# can.net
KiCad netlist of a schematic drawn in EAGLE
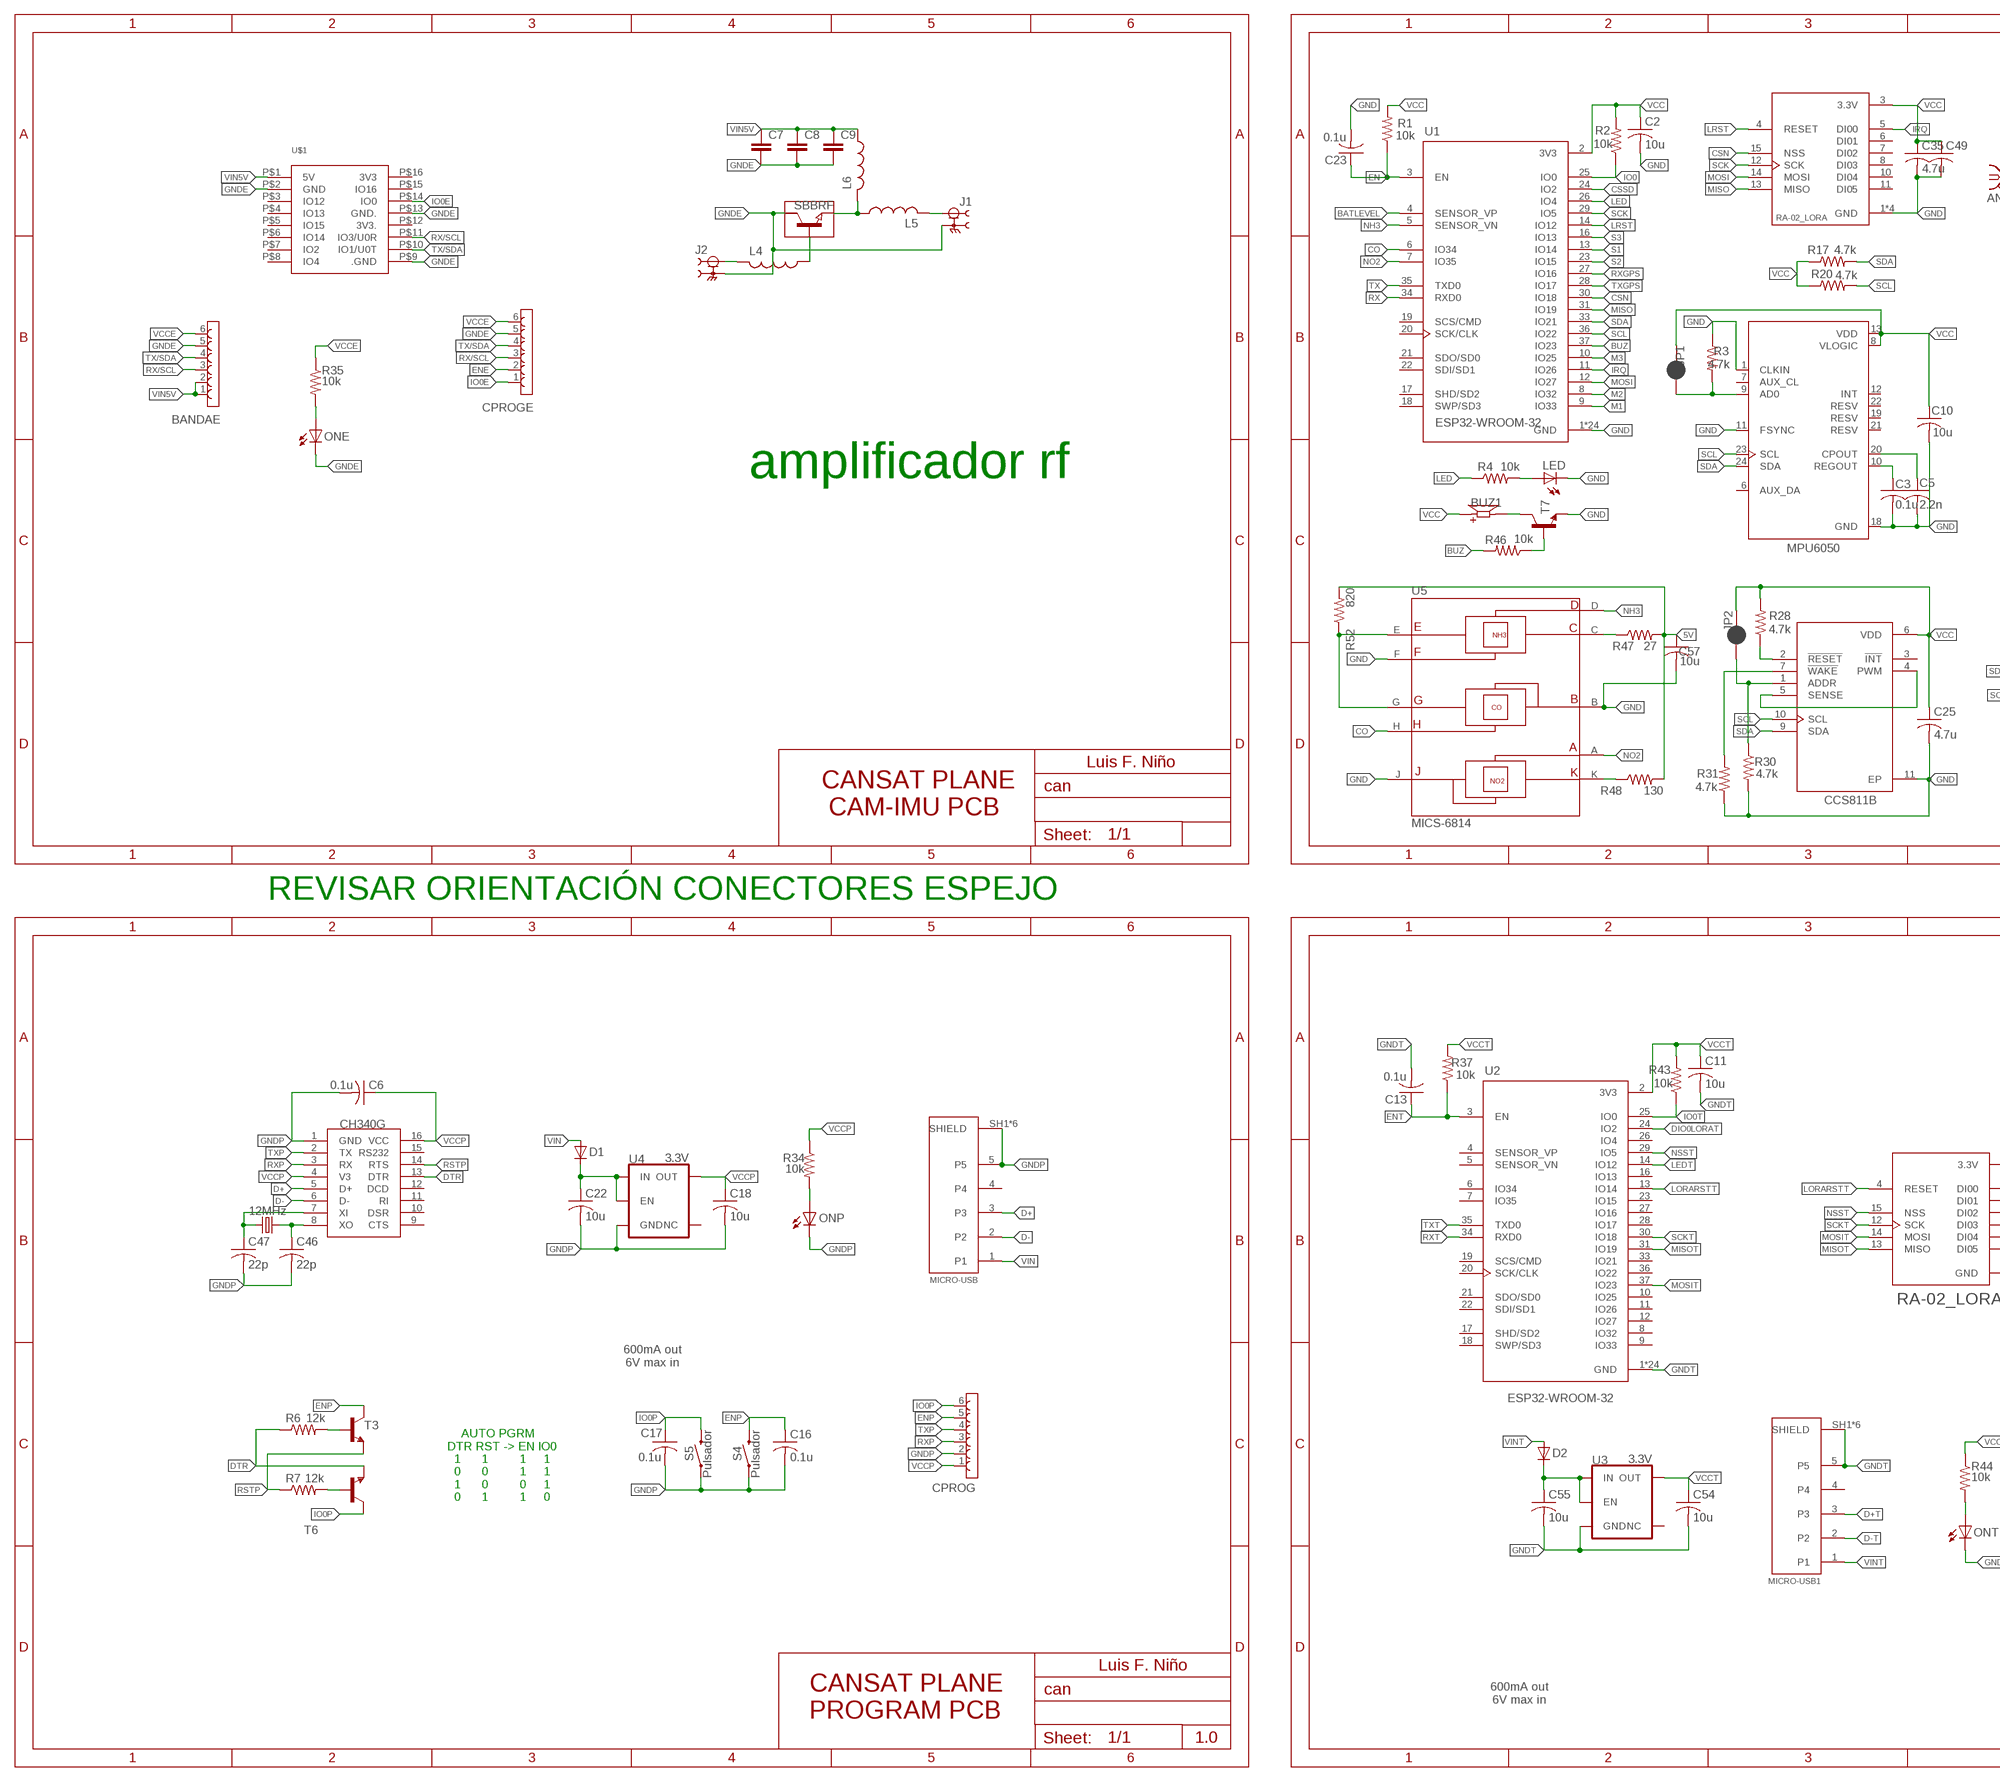
[diagram p0: schematic, sheet 1, part 1 of 2]
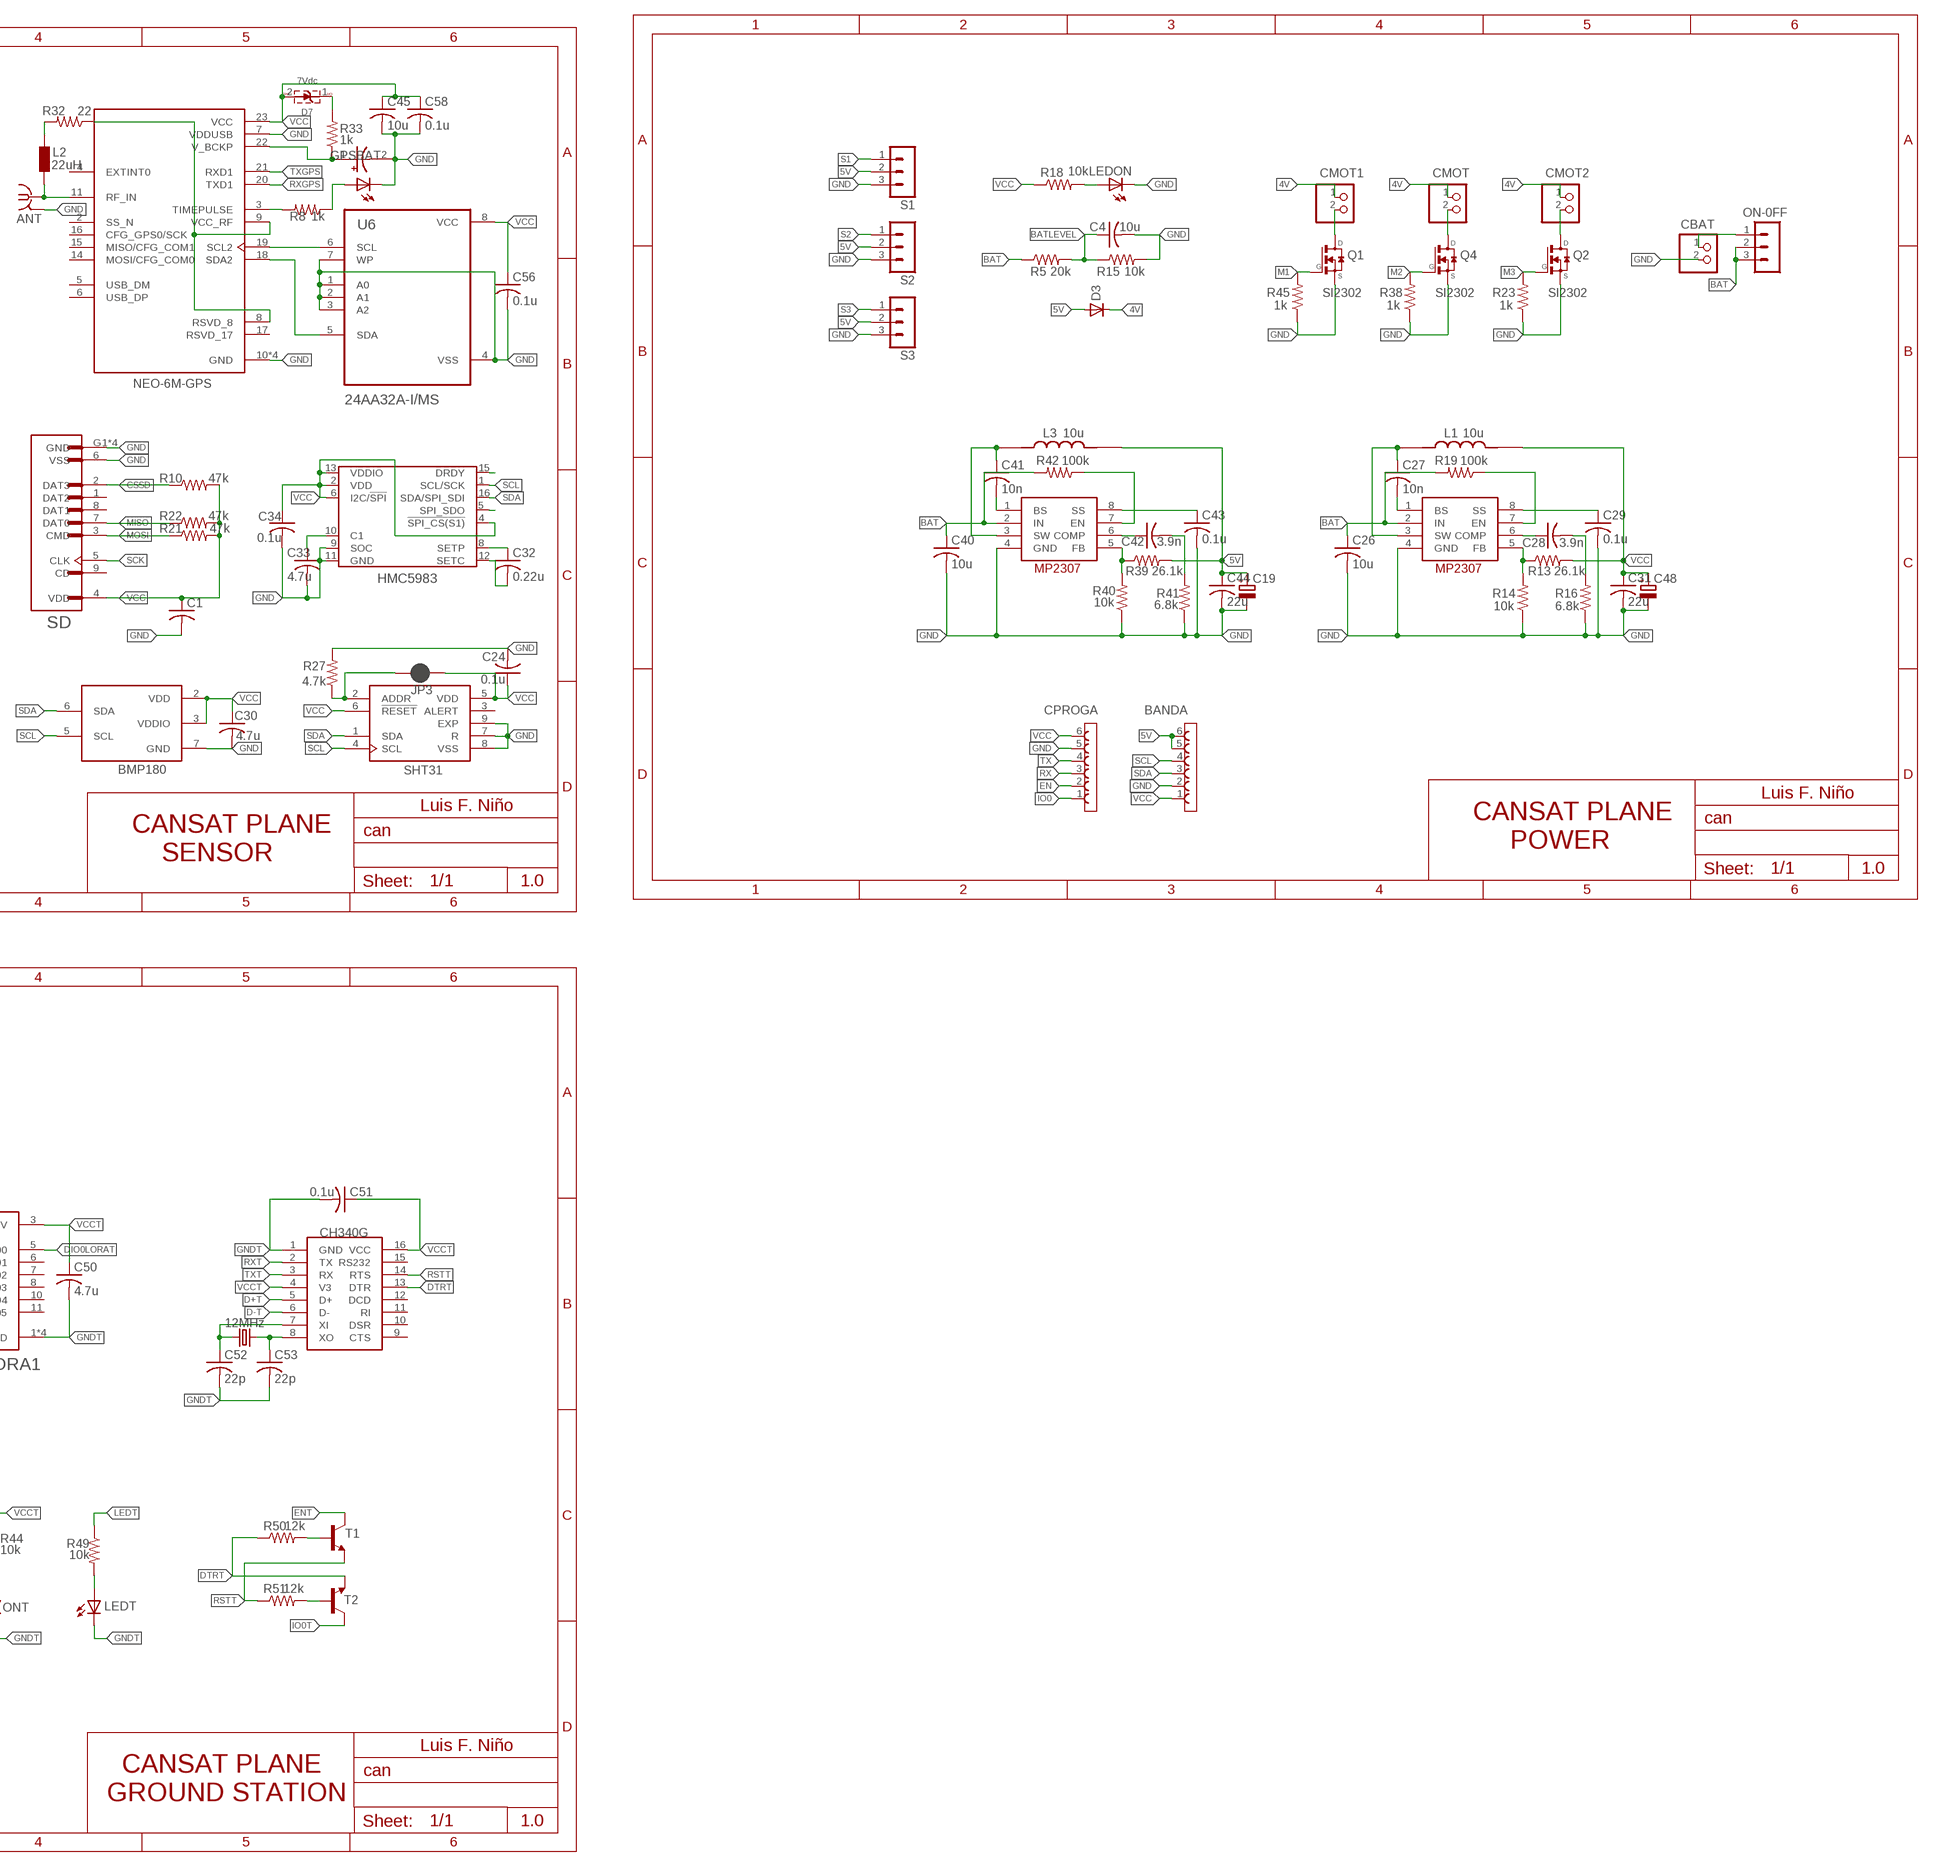
[diagram p1: schematic, sheet 1, part 2 of 2]

(export (version "E")
  (design (tool "Eeschema 10.0.6"))
  (components
    (comp (ref "BANDA")
      (value "68610614122")
      (footprint "eagle-import:68610614122")
      (fields (field (name "MF") "Wurth Electronics"))
      (libsource (lib "eagle-import") (part "68610614122"))
    )
    (comp (ref "BANDAE")
      (value "68610614122")
      (footprint "eagle-import:68610614122")
      (fields (field (name "MF") "Wurth Electronics"))
      (libsource (lib "eagle-import") (part "68610614122"))
    )
    (comp (ref "BMP180")
      (value "BMP180")
      (footprint "eagle-import:BMP180")
      (fields (field (name "MF") "Bosch Sensortec"))
      (libsource (lib "eagle-import") (part "BMP180"))
    )
    (comp (ref "BUZ1")
      (value "BUZ")
      (footprint "eagle-import:CUI_CMT-8530S-SMT")
      (fields (field (name "MF") "CUI Devices") (field (name "MP") "CMT-8530S-SMT-TR"))
      (libsource (lib "eagle-import") (part "CMT-8530S-SMT"))
    )
    (comp (ref "C1")
      (value "C-USC0805K")
      (footprint "eagle-import:C0805K")
      (libsource (lib "eagle-import") (part "C-USC0805K"))
    )
    (comp (ref "C2")
      (value "10u")
      (footprint "eagle-import:C1206")
      (libsource (lib "eagle-import") (part "C-USC1206"))
    )
    (comp (ref "C3")
      (value "0.1u")
      (footprint "eagle-import:C0603K")
      (libsource (lib "eagle-import") (part "C-USC0603K"))
    )
    (comp (ref "C4")
      (value "10u")
      (footprint "eagle-import:C0603K")
      (libsource (lib "eagle-import") (part "C-USC0603K"))
    )
    (comp (ref "C5")
      (value "2.2n")
      (footprint "eagle-import:C0603K")
      (libsource (lib "eagle-import") (part "C-USC0603K"))
    )
    (comp (ref "C6")
      (value "0.1u")
      (footprint "eagle-import:C1206")
      (libsource (lib "eagle-import") (part "C-USC1206"))
    )
    (comp (ref "C7")
      (value "C-EUC0805K")
      (footprint "eagle-import:C0805K")
      (libsource (lib "eagle-import") (part "C-EUC0805K"))
    )
    (comp (ref "C8")
      (value "C-EUC0805K")
      (footprint "eagle-import:C0805K")
      (libsource (lib "eagle-import") (part "C-EUC0805K"))
    )
    (comp (ref "C9")
      (value "C-EUC0805K")
      (footprint "eagle-import:C0805K")
      (libsource (lib "eagle-import") (part "C-EUC0805K"))
    )
    (comp (ref "C10")
      (value "10u")
      (footprint "eagle-import:C1206")
      (libsource (lib "eagle-import") (part "C-USC1206"))
    )
    (comp (ref "C11")
      (value "10u")
      (footprint "eagle-import:C1206")
      (libsource (lib "eagle-import") (part "C-USC1206"))
    )
    (comp (ref "C13")
      (value "0.1u")
      (footprint "eagle-import:C1206")
      (libsource (lib "eagle-import") (part "C-USC1206"))
    )
    (comp (ref "C16")
      (value "0.1u")
      (footprint "eagle-import:C0603K")
      (libsource (lib "eagle-import") (part "resistor_348_C-USC0603K"))
    )
    (comp (ref "C17")
      (value "0.1u")
      (footprint "eagle-import:C0603K")
      (libsource (lib "eagle-import") (part "resistor_348_C-USC0603K"))
    )
    (comp (ref "C18")
      (value "10u")
      (footprint "eagle-import:C1206")
      (libsource (lib "eagle-import") (part "C-USC1206"))
    )
    (comp (ref "C19")
      (value "CPOL-EU153CLV-0605")
      (footprint "eagle-import:153CLV-0605")
      (libsource (lib "eagle-import") (part "CPOL-EU153CLV-0605"))
    )
    (comp (ref "C22")
      (value "10u")
      (footprint "eagle-import:C1206")
      (libsource (lib "eagle-import") (part "C-USC1206"))
    )
    (comp (ref "C23")
      (value "0.1u")
      (footprint "eagle-import:C1206")
      (libsource (lib "eagle-import") (part "C-USC1206"))
    )
    (comp (ref "C24")
      (value "0.1u")
      (footprint "eagle-import:C1206")
      (libsource (lib "eagle-import") (part "C-USC1206"))
    )
    (comp (ref "C25")
      (value "4.7u")
      (footprint "eagle-import:C1206")
      (libsource (lib "eagle-import") (part "C-USC1206"))
    )
    (comp (ref "C26")
      (value "10u")
      (footprint "eagle-import:C1206")
      (libsource (lib "eagle-import") (part "C-USC1206"))
    )
    (comp (ref "C27")
      (value "10n")
      (footprint "eagle-import:C0805")
      (libsource (lib "eagle-import") (part "C-USC0805"))
    )
    (comp (ref "C28")
      (value "3.9n")
      (footprint "eagle-import:C0805")
      (libsource (lib "eagle-import") (part "C-USC0805"))
    )
    (comp (ref "C29")
      (value "0.1u")
      (footprint "eagle-import:C0805")
      (libsource (lib "eagle-import") (part "C-USC0805"))
    )
    (comp (ref "C30")
      (value "4.7u")
      (footprint "eagle-import:C1206")
      (libsource (lib "eagle-import") (part "C-USC1206"))
    )
    (comp (ref "C31")
      (value "22u")
      (footprint "eagle-import:C1206")
      (libsource (lib "eagle-import") (part "C-USC1206"))
    )
    (comp (ref "C32")
      (value "0.22u")
      (footprint "eagle-import:C0603K")
      (libsource (lib "eagle-import") (part "C-USC0603K"))
    )
    (comp (ref "C33")
      (value "4.7u")
      (footprint "eagle-import:C0603K")
      (libsource (lib "eagle-import") (part "C-USC0603K"))
    )
    (comp (ref "C34")
      (value "0.1u")
      (footprint "eagle-import:C1206")
      (libsource (lib "eagle-import") (part "C-USC1206"))
    )
    (comp (ref "C35")
      (value "4.7u")
      (footprint "eagle-import:C1206")
      (libsource (lib "eagle-import") (part "C-USC1206"))
    )
    (comp (ref "C40")
      (value "10u")
      (footprint "eagle-import:C1206")
      (libsource (lib "eagle-import") (part "C-USC1206"))
    )
    (comp (ref "C41")
      (value "10n")
      (footprint "eagle-import:C0805")
      (libsource (lib "eagle-import") (part "C-USC0805"))
    )
    (comp (ref "C42")
      (value "3.9n")
      (footprint "eagle-import:C0805")
      (libsource (lib "eagle-import") (part "C-USC0805"))
    )
    (comp (ref "C43")
      (value "0.1u")
      (footprint "eagle-import:C0805")
      (libsource (lib "eagle-import") (part "C-USC0805"))
    )
    (comp (ref "C44")
      (value "22u")
      (footprint "eagle-import:C1206")
      (libsource (lib "eagle-import") (part "C-USC1206"))
    )
    (comp (ref "C45")
      (value "10u")
      (footprint "eagle-import:C1206")
      (libsource (lib "eagle-import") (part "C-USC1206"))
    )
    (comp (ref "C46")
      (value "22p")
      (footprint "eagle-import:C1206")
      (libsource (lib "eagle-import") (part "C-USC1206"))
    )
    (comp (ref "C47")
      (value "22p")
      (footprint "eagle-import:C1206")
      (libsource (lib "eagle-import") (part "C-USC1206"))
    )
    (comp (ref "C48")
      (value "CPOL-EU153CLV-0605")
      (footprint "eagle-import:153CLV-0605")
      (libsource (lib "eagle-import") (part "CPOL-EU153CLV-0605"))
    )
    (comp (ref "C49")
      (value "C-USC0805K")
      (footprint "eagle-import:C0805K")
      (libsource (lib "eagle-import") (part "C-USC0805K"))
    )
    (comp (ref "C50")
      (value "4.7u")
      (footprint "eagle-import:C1206")
      (libsource (lib "eagle-import") (part "C-USC1206"))
    )
    (comp (ref "C51")
      (value "0.1u")
      (footprint "eagle-import:C1206")
      (libsource (lib "eagle-import") (part "C-USC1206"))
    )
    (comp (ref "C52")
      (value "22p")
      (footprint "eagle-import:C1206")
      (libsource (lib "eagle-import") (part "C-USC1206"))
    )
    (comp (ref "C53")
      (value "22p")
      (footprint "eagle-import:C1206")
      (libsource (lib "eagle-import") (part "C-USC1206"))
    )
    (comp (ref "C54")
      (value "10u")
      (footprint "eagle-import:C1206")
      (libsource (lib "eagle-import") (part "C-USC1206"))
    )
    (comp (ref "C55")
      (value "10u")
      (footprint "eagle-import:C1206")
      (libsource (lib "eagle-import") (part "C-USC1206"))
    )
    (comp (ref "C56")
      (value "0.1u")
      (footprint "eagle-import:C0805K")
      (libsource (lib "eagle-import") (part "C-USC0805K"))
    )
    (comp (ref "C57")
      (value "10u")
      (footprint "eagle-import:C1206")
      (libsource (lib "eagle-import") (part "C-USC1206"))
    )
    (comp (ref "C58")
      (value "0.1u")
      (footprint "eagle-import:C0805K")
      (libsource (lib "eagle-import") (part "C-USC0805K"))
    )
    (comp (ref "CBAT")
      (value "PINHD-1X2")
      (footprint "eagle-import:1X02")
      (libsource (lib "eagle-import") (part "PINHD-1X2"))
    )
    (comp (ref "CCS811B")
      (value "CCS811B-JOPD500")
      (footprint "eagle-import:SON60P400X270X110-11N")
      (fields (field (name "MF") "ScioSense"))
      (libsource (lib "eagle-import") (part "CCS811B-JOPD500"))
    )
    (comp (ref "CH1")
      (value "CH340")
      (footprint "eagle-import:SOIC127P600X175-16N")
      (fields (field (name "MF") "WCH") (field (name "MP") "Ch340G"))
      (libsource (lib "eagle-import") (part "CH340G"))
    )
    (comp (ref "CH340")
      (value "CH340")
      (footprint "eagle-import:SOIC127P600X175-16N")
      (fields (field (name "MF") "WCH") (field (name "MP") "Ch340G"))
      (libsource (lib "eagle-import") (part "CH340G"))
    )
    (comp (ref "CMOT")
      (value "PINHD-1X2")
      (footprint "eagle-import:1X02")
      (libsource (lib "eagle-import") (part "PINHD-1X2"))
    )
    (comp (ref "CMOT1")
      (value "PINHD-1X2")
      (footprint "eagle-import:1X02")
      (libsource (lib "eagle-import") (part "PINHD-1X2"))
    )
    (comp (ref "CMOT2")
      (value "PINHD-1X2")
      (footprint "eagle-import:1X02")
      (libsource (lib "eagle-import") (part "PINHD-1X2"))
    )
    (comp (ref "CPROG")
      (value "68610614122")
      (footprint "eagle-import:68610614122")
      (fields (field (name "MF") "Wurth Electronics"))
      (libsource (lib "eagle-import") (part "68610614122"))
    )
    (comp (ref "CPROGA")
      (value "68610614122")
      (footprint "eagle-import:68610614122")
      (fields (field (name "MF") "Wurth Electronics"))
      (libsource (lib "eagle-import") (part "68610614122"))
    )
    (comp (ref "CPROGE")
      (value "68610614122")
      (footprint "eagle-import:68610614122")
      (fields (field (name "MF") "Wurth Electronics"))
      (libsource (lib "eagle-import") (part "68610614122"))
    )
    (comp (ref "D1")
      (value "CGRM4005-G")
      (footprint "eagle-import:SOD-123_MINI-SMA")
      (libsource (lib "eagle-import") (part "CGRM400-G5"))
    )
    (comp (ref "D2")
      (value "CGRM4005-G")
      (footprint "eagle-import:SOD-123_MINI-SMA")
      (libsource (lib "eagle-import") (part "CGRM400-G5"))
    )
    (comp (ref "D3")
      (value "CGRM4005-G")
      (footprint "eagle-import:SOD-123_MINI-SMA")
      (libsource (lib "eagle-import") (part "CGRM400-G5"))
    )
    (comp (ref "D7")
      (value "7Vdc")
      (footprint "eagle-import:WE-TVS_DFN1610-2L")
      (libsource (lib "eagle-import") (part "WE-TVS_DFN1610-2L_824045817"))
    )
    (comp (ref "GPSBAT")
      (value "XH414H")
      (footprint "eagle-import:CAP_XH414H-IV01E")
      (fields (field (name "MF") "Seiko Instruments") (field (name "MP") "XH414H-IV01E"))
      (libsource (lib "eagle-import") (part "XH414H-IV01E"))
    )
    (comp (ref "HMC5983")
      (value "HMC5983")
      (footprint "eagle-import:HMC5983")
      (fields (field (name "MF") "Honeywell Aerospace") (field (name "MP") "HMC5983-T"))
      (libsource (lib "eagle-import") (part "HMC5983"))
    )
    (comp (ref "IC2")
      (value "MP2307")
      (footprint "eagle-import:SO8-TH")
      (fields (field (name "MF") "Monolithic Power"))
      (libsource (lib "eagle-import") (part "MP2307"))
    )
    (comp (ref "IC4")
      (value "MP2307")
      (footprint "eagle-import:SO8-TH")
      (fields (field (name "MF") "Monolithic Power"))
      (libsource (lib "eagle-import") (part "MP2307"))
    )
    (comp (ref "J1")
      (value "CONSMA003.031-G")
      (footprint "eagle-import:LINX_CONSMA003.031-G")
      (fields (field (name "MF") "Linx Technologies"))
      (libsource (lib "eagle-import") (part "CONSMA003.031-G"))
    )
    (comp (ref "J2")
      (value "CONSMA003.031-G")
      (footprint "eagle-import:LINX_CONSMA003.031-G")
      (fields (field (name "MF") "Linx Technologies"))
      (libsource (lib "eagle-import") (part "CONSMA003.031-G"))
    )
    (comp (ref "JP1")
      (value "JUMPER-SMT_2_NC_PASTE_SILK")
      (footprint "eagle-import:SMT-JUMPER_2_NC_PASTE_SILK")
      (libsource (lib "eagle-import") (part "JUMPER-SMT_2_NC_PASTE_SILK"))
    )
    (comp (ref "JP2")
      (value "JUMPER-SMT_2_NC_PASTE_SILK")
      (footprint "eagle-import:SMT-JUMPER_2_NC_PASTE_SILK")
      (libsource (lib "eagle-import") (part "JUMPER-SMT_2_NC_PASTE_SILK"))
    )
    (comp (ref "JP3")
      (value "JUMPER-SMT_2_NC_PASTE_SILK")
      (footprint "eagle-import:SMT-JUMPER_2_NC_PASTE_SILK")
      (libsource (lib "eagle-import") (part "JUMPER-SMT_2_NC_PASTE_SILK"))
    )
    (comp (ref "L1")
      (value "10u")
      (footprint "eagle-import:IND_FDVE0630-H-100M=P3")
      (fields (field (name "MF") "Murata") (field (name "MP") "FDVE0630-H-100M=P3"))
      (libsource (lib "eagle-import") (part "FDVE0630-H-100M=P3"))
    )
    (comp (ref "L2")
      (value "22uH")
      (footprint "eagle-import:L2012C")
      (libsource (lib "eagle-import") (part "LL2012C"))
    )
    (comp (ref "L3")
      (value "10u")
      (footprint "eagle-import:IND_FDVE0630-H-100M=P3")
      (fields (field (name "MF") "Murata") (field (name "MP") "FDVE0630-H-100M=P3"))
      (libsource (lib "eagle-import") (part "FDVE0630-H-100M=P3"))
    )
    (comp (ref "L4")
      (value "L-USL2012C")
      (footprint "eagle-import:L2012C")
      (libsource (lib "eagle-import") (part "L-USL2012C"))
    )
    (comp (ref "L5")
      (value "L-USL2012C")
      (footprint "eagle-import:L2012C")
      (libsource (lib "eagle-import") (part "L-USL2012C"))
    )
    (comp (ref "L6")
      (value "L-USL3225P")
      (footprint "eagle-import:L3225P")
      (libsource (lib "eagle-import") (part "L-USL3225P"))
    )
    (comp (ref "LED")
      (value "LEDCHIPLED_0805")
      (footprint "eagle-import:CHIPLED_0805")
      (libsource (lib "eagle-import") (part "LEDCHIPLED_0805"))
    )
    (comp (ref "LED1")
      (value "LEDCHIPLED_0805")
      (footprint "eagle-import:CHIPLED_0805")
      (libsource (lib "eagle-import") (part "LEDCHIPLED_0805"))
    )
    (comp (ref "LEDON")
      (value "LEDCHIPLED_0805")
      (footprint "eagle-import:CHIPLED_0805")
      (libsource (lib "eagle-import") (part "LEDCHIPLED_0805"))
    )
    (comp (ref "LEDT")
      (value "LEDCHIPLED_0805")
      (footprint "eagle-import:CHIPLED_0805")
      (libsource (lib "eagle-import") (part "LEDCHIPLED_0805"))
    )
    (comp (ref "MICRO-USB")
      (value "1932788-1")
      (footprint "eagle-import:TE_1932788-1")
      (fields (field (name "MF") "TE Connectivity"))
      (libsource (lib "eagle-import") (part "1932788-1"))
    )
    (comp (ref "MICRO-USB1")
      (value "1932788-1")
      (footprint "eagle-import:TE_1932788-1")
      (fields (field (name "MF") "TE Connectivity"))
      (libsource (lib "eagle-import") (part "1932788-1"))
    )
    (comp (ref "MPU6050")
      (value "MPU-6050")
      (footprint "eagle-import:QFN50P400X400X95-24N")
      (fields (field (name "MF") "TDK InvenSense"))
      (libsource (lib "eagle-import") (part "MPU-6050"))
    )
    (comp (ref "NEO-6M-GPS")
      (value "NEO-6M-GPS")
      (footprint "eagle-import:XCVR_NEO-6M-GPS")
      (fields (field (name "MF") "u-blox"))
      (libsource (lib "eagle-import") (part "NEO-6M-GPS"))
    )
    (comp (ref "ON-0FF")
      (value "MA03-1")
      (footprint "eagle-import:MA03-1")
      (libsource (lib "eagle-import") (part "MA03-1"))
    )
    (comp (ref "ONE")
      (value "LEDCHIPLED_0805")
      (footprint "eagle-import:CHIPLED_0805")
      (libsource (lib "eagle-import") (part "LEDCHIPLED_0805"))
    )
    (comp (ref "ONP")
      (value "LEDCHIPLED_0805")
      (footprint "eagle-import:CHIPLED_0805")
      (libsource (lib "eagle-import") (part "LEDCHIPLED_0805"))
    )
    (comp (ref "ONT")
      (value "LEDCHIPLED_0805")
      (footprint "eagle-import:CHIPLED_0805")
      (libsource (lib "eagle-import") (part "LEDCHIPLED_0805"))
    )
    (comp (ref "Q1")
      (value "SI2302")
      (footprint "eagle-import:SOT23")
      (fields (field (name "MF") "Vishay Siliconix"))
      (libsource (lib "eagle-import") (part "SI2302"))
    )
    (comp (ref "Q2")
      (value "SI2302")
      (footprint "eagle-import:SOT23")
      (fields (field (name "MF") "Vishay Siliconix"))
      (libsource (lib "eagle-import") (part "SI2302"))
    )
    (comp (ref "Q4")
      (value "SI2302")
      (footprint "eagle-import:SOT23")
      (fields (field (name "MF") "Vishay Siliconix"))
      (libsource (lib "eagle-import") (part "SI2302"))
    )
    (comp (ref "R1")
      (value "10k")
      (footprint "eagle-import:R0603")
      (libsource (lib "eagle-import") (part "resistor_348_R-US_R0603"))
    )
    (comp (ref "R2")
      (value "10k")
      (footprint "eagle-import:R0603")
      (libsource (lib "eagle-import") (part "resistor_348_R-US_R0603"))
    )
    (comp (ref "R3")
      (value "4.7k")
      (footprint "eagle-import:R0603")
      (libsource (lib "eagle-import") (part "R-US_R0603"))
    )
    (comp (ref "R4")
      (value "10k")
      (footprint "eagle-import:R0603")
      (libsource (lib "eagle-import") (part "resistor_348_R-US_R0603"))
    )
    (comp (ref "R5")
      (value "20k")
      (footprint "eagle-import:R0603")
      (libsource (lib "eagle-import") (part "resistor_348_R-US_R0603"))
    )
    (comp (ref "R6")
      (value "12k")
      (footprint "eagle-import:R0603")
      (libsource (lib "eagle-import") (part "resistor_348_R-US_R0603"))
    )
    (comp (ref "R7")
      (value "12k")
      (footprint "eagle-import:R0603")
      (libsource (lib "eagle-import") (part "resistor_348_R-US_R0603"))
    )
    (comp (ref "R8")
      (value "1k")
      (footprint "eagle-import:R0603")
      (libsource (lib "eagle-import") (part "resistor_348_R-US_R0603"))
    )
    (comp (ref "R10")
      (value "47k")
      (footprint "eagle-import:R0603")
      (libsource (lib "eagle-import") (part "resistor_348_R-US_R0603"))
    )
    (comp (ref "R13")
      (value "26.1k")
      (footprint "eagle-import:M0805")
      (libsource (lib "eagle-import") (part "R-US_M0805"))
    )
    (comp (ref "R14")
      (value "10k")
      (footprint "eagle-import:R0603")
      (libsource (lib "eagle-import") (part "resistor_348_R-US_R0603"))
    )
    (comp (ref "R15")
      (value "10k")
      (footprint "eagle-import:R0603")
      (libsource (lib "eagle-import") (part "resistor_348_R-US_R0603"))
    )
    (comp (ref "R16")
      (value "6.8k")
      (footprint "eagle-import:R0603")
      (libsource (lib "eagle-import") (part "resistor_348_R-US_R0603"))
    )
    (comp (ref "R17")
      (value "4.7k")
      (footprint "eagle-import:R0603")
      (libsource (lib "eagle-import") (part "resistor_348_R-US_R0603"))
    )
    (comp (ref "R18")
      (value "10k")
      (footprint "eagle-import:R0603")
      (libsource (lib "eagle-import") (part "resistor_348_R-US_R0603"))
    )
    (comp (ref "R19")
      (value "100k")
      (footprint "eagle-import:R0603")
      (libsource (lib "eagle-import") (part "resistor_348_R-US_R0603"))
    )
    (comp (ref "R20")
      (value "4.7k")
      (footprint "eagle-import:R0603")
      (libsource (lib "eagle-import") (part "resistor_348_R-US_R0603"))
    )
    (comp (ref "R21")
      (value "47k")
      (footprint "eagle-import:R0603")
      (libsource (lib "eagle-import") (part "resistor_348_R-US_R0603"))
    )
    (comp (ref "R22")
      (value "47k")
      (footprint "eagle-import:R0603")
      (libsource (lib "eagle-import") (part "resistor_348_R-US_R0603"))
    )
    (comp (ref "R23")
      (value "1k")
      (footprint "eagle-import:R0603")
      (libsource (lib "eagle-import") (part "resistor_348_R-US_R0603"))
    )
    (comp (ref "R27")
      (value "4.7k")
      (footprint "eagle-import:R0603")
      (libsource (lib "eagle-import") (part "resistor_348_R-US_R0603"))
    )
    (comp (ref "R28")
      (value "4.7k")
      (footprint "eagle-import:R0603")
      (libsource (lib "eagle-import") (part "resistor_348_R-US_R0603"))
    )
    (comp (ref "R30")
      (value "4.7k")
      (footprint "eagle-import:R0603")
      (libsource (lib "eagle-import") (part "resistor_348_R-US_R0603"))
    )
    (comp (ref "R31")
      (value "4.7k")
      (footprint "eagle-import:R0603")
      (libsource (lib "eagle-import") (part "resistor_348_R-US_R0603"))
    )
    (comp (ref "R32")
      (value "22")
      (footprint "eagle-import:R0603")
      (libsource (lib "eagle-import") (part "resistor_348_R-US_R0603"))
    )
    (comp (ref "R33")
      (value "1k")
      (footprint "eagle-import:R0603")
      (libsource (lib "eagle-import") (part "resistor_348_R-US_R0603"))
    )
    (comp (ref "R34")
      (value "10k")
      (footprint "eagle-import:R0603")
      (libsource (lib "eagle-import") (part "resistor_348_R-US_R0603"))
    )
    (comp (ref "R35")
      (value "10k")
      (footprint "eagle-import:R0603")
      (libsource (lib "eagle-import") (part "resistor_348_R-US_R0603"))
    )
    (comp (ref "R37")
      (value "10k")
      (footprint "eagle-import:R0603")
      (libsource (lib "eagle-import") (part "resistor_348_R-US_R0603"))
    )
    (comp (ref "R38")
      (value "1k")
      (footprint "eagle-import:R0603")
      (libsource (lib "eagle-import") (part "resistor_348_R-US_R0603"))
    )
    (comp (ref "R39")
      (value "26.1k")
      (footprint "eagle-import:M0805")
      (libsource (lib "eagle-import") (part "R-US_M0805"))
    )
    (comp (ref "R40")
      (value "10k")
      (footprint "eagle-import:R0603")
      (libsource (lib "eagle-import") (part "resistor_348_R-US_R0603"))
    )
    (comp (ref "R41")
      (value "6.8k")
      (footprint "eagle-import:R0603")
      (libsource (lib "eagle-import") (part "resistor_348_R-US_R0603"))
    )
    (comp (ref "R42")
      (value "100k")
      (footprint "eagle-import:R0603")
      (libsource (lib "eagle-import") (part "resistor_348_R-US_R0603"))
    )
    (comp (ref "R43")
      (value "10k")
      (footprint "eagle-import:R0603")
      (libsource (lib "eagle-import") (part "resistor_348_R-US_R0603"))
    )
    (comp (ref "R44")
      (value "10k")
      (footprint "eagle-import:R0603")
      (libsource (lib "eagle-import") (part "resistor_348_R-US_R0603"))
    )
    (comp (ref "R45")
      (value "1k")
      (footprint "eagle-import:R0603")
      (libsource (lib "eagle-import") (part "resistor_348_R-US_R0603"))
    )
    (comp (ref "R46")
      (value "10k")
      (footprint "eagle-import:R0603")
      (libsource (lib "eagle-import") (part "resistor_348_R-US_R0603"))
    )
    (comp (ref "R47")
      (value "27")
      (footprint "eagle-import:R0603")
      (libsource (lib "eagle-import") (part "resistor_348_R-US_R0603"))
    )
    (comp (ref "R48")
      (value "130")
      (footprint "eagle-import:R0603")
      (libsource (lib "eagle-import") (part "resistor_348_R-US_R0603"))
    )
    (comp (ref "R49")
      (value "10k")
      (footprint "eagle-import:R0603")
      (libsource (lib "eagle-import") (part "resistor_348_R-US_R0603"))
    )
    (comp (ref "R50")
      (value "12k")
      (footprint "eagle-import:R0603")
      (libsource (lib "eagle-import") (part "resistor_348_R-US_R0603"))
    )
    (comp (ref "R51")
      (value "12k")
      (footprint "eagle-import:R0603")
      (libsource (lib "eagle-import") (part "resistor_348_R-US_R0603"))
    )
    (comp (ref "R52")
      (value "820")
      (footprint "eagle-import:R0603")
      (libsource (lib "eagle-import") (part "resistor_348_R-US_R0603"))
    )
    (comp (ref "RA-02_LORA")
      (value "RA-02_LORA")
      (footprint "eagle-import:MODULE_RA-02_LORA")
      (fields (field (name "MF") "AI-Thinker") (field (name "MP") "Ra-02 LoRa"))
      (libsource (lib "eagle-import") (part "RA-02_LORA"))
    )
    (comp (ref "RA-02_LORA1")
      (value "RA-02_LORA")
      (footprint "eagle-import:MODULE_RA-02_LORA")
      (fields (field (name "MF") "AI-Thinker") (field (name "MP") "Ra-02 LoRa"))
      (libsource (lib "eagle-import") (part "RA-02_LORA"))
    )
    (comp (ref "S1")
      (value "MA03-1")
      (footprint "eagle-import:MA03-1")
      (libsource (lib "eagle-import") (part "MA03-1"))
    )
    (comp (ref "S2")
      (value "MA03-1")
      (footprint "eagle-import:MA03-1")
      (libsource (lib "eagle-import") (part "MA03-1"))
    )
    (comp (ref "S3")
      (value "MA03-1")
      (footprint "eagle-import:MA03-1")
      (libsource (lib "eagle-import") (part "MA03-1"))
    )
    (comp (ref "S4")
      (value "Pulsador")
      (footprint "eagle-import:TACTILE_SWITCH_SMD_RIGHT_ANGLE")
      (libsource (lib "eagle-import") (part "MOMENTARY-SWITCH-SPST-SMD-RIGHT-ANGLE"))
    )
    (comp (ref "S5")
      (value "Pulsador")
      (footprint "eagle-import:TACTILE_SWITCH_SMD_RIGHT_ANGLE")
      (libsource (lib "eagle-import") (part "MOMENTARY-SWITCH-SPST-SMD-RIGHT-ANGLE"))
    )
    (comp (ref "SBBRF")
      (value "NPN-TRANSISTIOR-2COLSOT89")
      (footprint "eagle-import:SOT89")
      (libsource (lib "eagle-import") (part "NPN-TRANSISTIOR-2COLSOT89"))
    )
    (comp (ref "SD")
      (value "ST-TF-003A")
      (footprint "eagle-import:SUNTECH_ST-TF-003A")
      (fields (field (name "MF") "Suntech"))
      (libsource (lib "eagle-import") (part "ST-TF-003A"))
    )
    (comp (ref "SHT31")
      (value "SHT31-DIS-B")
      (footprint "eagle-import:SON50P250X250X100-9N")
      (fields (field (name "MF") "Sensirion AG"))
      (libsource (lib "eagle-import") (part "SHT31-DIS-B"))
    )
    (comp (ref "T1")
      (value "MMBT2222ALT1-NPN-SOT23-BEC")
      (footprint "eagle-import:SOT23-BEC")
      (libsource (lib "eagle-import") (part "transistor_402_-NPN-SOT23-BECMMBT2222ALT1"))
    )
    (comp (ref "T2")
      (value "MMBT2222ALT1-NPN-SOT23-BEC")
      (footprint "eagle-import:SOT23-BEC")
      (libsource (lib "eagle-import") (part "transistor_402_-NPN-SOT23-BECMMBT2222ALT1"))
    )
    (comp (ref "T3")
      (value "MMBT2222ALT1-NPN-SOT23-BEC")
      (footprint "eagle-import:SOT23-BEC")
      (libsource (lib "eagle-import") (part "transistor_402_-NPN-SOT23-BECMMBT2222ALT1"))
    )
    (comp (ref "T6")
      (value "MMBT2222ALT1-NPN-SOT23-BEC")
      (footprint "eagle-import:SOT23-BEC")
      (libsource (lib "eagle-import") (part "transistor_402_-NPN-SOT23-BECMMBT2222ALT1"))
    )
    (comp (ref "T7")
      (value "MMBT2222ALT1-NPN-SOT23-BEC")
      (footprint "eagle-import:SOT23-BEC")
      (libsource (lib "eagle-import") (part "-NPN-SOT23-BECMMBT2222ALT1"))
    )
    (comp (ref "U$1")
      (value "ESP32-CAM")
      (footprint "eagle-import:ESP32-CAM")
      (fields (field (name "MF") "AI-Thinker"))
      (libsource (lib "eagle-import") (part "ESP32-CAM"))
    )
    (comp (ref "U1")
      (value "ESP32-WROOM-32")
      (footprint "eagle-import:MODULE_ESP32-WROOM-32")
      (fields (field (name "MF") "Espressif Systems") (field (name "SPICEPREFIX") "X"))
      (libsource (lib "eagle-import") (part "ESP32-WROOM-32"))
    )
    (comp (ref "U2")
      (value "ESP32-WROOM-32")
      (footprint "eagle-import:MODULE_ESP32-WROOM-32")
      (fields (field (name "MF") "Espressif Systems"))
      (libsource (lib "eagle-import") (part "ESP32-WROOM-32"))
    )
    (comp (ref "U3")
      (value "3.3V")
      (footprint "eagle-import:SOT23-5")
      (libsource (lib "eagle-import") (part "V_REG_AP2112K-3.3V"))
    )
    (comp (ref "U4")
      (value "3.3V")
      (footprint "eagle-import:SOT23-5")
      (libsource (lib "eagle-import") (part "V_REG_AP2112K-3.3V"))
    )
    (comp (ref "U5")
      (value "MICS-6814")
      (footprint "eagle-import:SENSOR_MICS-6814")
      (fields (field (name "MF") "Amphenol SGX Sensortech"))
      (libsource (lib "eagle-import") (part "MICS-6814"))
    )
    (comp (ref "U6")
      (value "24AA32A-I/MS")
      (footprint "eagle-import:SOP65P490X110-8N")
      (fields (field (name "MF") "Microchip"))
      (libsource (lib "eagle-import") (part "24AA32A-I/MS"))
    )
    (comp (ref "X2")
      (value "ANT")
      (footprint "eagle-import:MC-921")
      (libsource (lib "eagle-import") (part "MC-921"))
    )
    (comp (ref "Y2")
      (value "12MHz")
      (footprint "eagle-import:CRYSTAL-SMD-3.2X2.5MM")
      (libsource (lib "eagle-import") (part "CRYSTALSMD-3.2X2.5"))
    )
    (comp (ref "Y3")
      (value "12MHz")
      (footprint "eagle-import:CRYSTAL-SMD-3.2X2.5MM")
      (libsource (lib "eagle-import") (part "CRYSTALSMD-3.2X2.5"))
    )
  )
  (nets
    (net (code "1") (name "4V") (class "Default")
      (node (ref "CMOT") (pin "1") (pinfunction "1_1") (pintype "passive"))
      (node (ref "CMOT1") (pin "1") (pinfunction "1_1") (pintype "passive"))
      (node (ref "CMOT2") (pin "1") (pinfunction "1_1") (pintype "passive"))
      (node (ref "D3") (pin "C") (pinfunction "C_C") (pintype "passive"))
    )
    (net (code "2") (name "5V") (class "Default")
      (node (ref "BANDA") (pin "5") (pinfunction "2_5") (pintype "passive"))
      (node (ref "BANDA") (pin "6") (pinfunction "1_6") (pintype "passive"))
      (node (ref "C19") (pin "+") (pinfunction "+_+") (pintype "passive"))
      (node (ref "C44") (pin "1") (pinfunction "1_1") (pintype "passive"))
      (node (ref "C57") (pin "1") (pinfunction "1_1") (pintype "passive"))
      (node (ref "D3") (pin "A") (pinfunction "A_A") (pintype "passive"))
      (node (ref "L3") (pin "2") (pinfunction "2_2") (pintype "passive"))
      (node (ref "R39") (pin "2") (pinfunction "2_2") (pintype "passive"))
      (node (ref "R47") (pin "2") (pinfunction "2_2") (pintype "passive"))
      (node (ref "R48") (pin "2") (pinfunction "2_2") (pintype "passive"))
      (node (ref "R52") (pin "2") (pinfunction "2_2") (pintype "passive"))
      (node (ref "S1") (pin "2") (pinfunction "2_2") (pintype "passive"))
      (node (ref "S2") (pin "2") (pinfunction "2_2") (pintype "passive"))
      (node (ref "S3") (pin "2") (pinfunction "2_2") (pintype "passive"))
    )
    (net (code "3") (name "BAT") (class "Default")
      (node (ref "C26") (pin "1") (pinfunction "1_1") (pintype "passive"))
      (node (ref "C40") (pin "1") (pinfunction "1_1") (pintype "passive"))
      (node (ref "IC2") (pin "2") (pinfunction "IN_2") (pintype "bidirectional"))
      (node (ref "IC4") (pin "2") (pinfunction "IN_2") (pintype "bidirectional"))
      (node (ref "ON-0FF") (pin "2") (pinfunction "2_2") (pintype "passive"))
      (node (ref "ON-0FF") (pin "3") (pinfunction "3_3") (pintype "passive"))
      (node (ref "R19") (pin "2") (pinfunction "2_2") (pintype "passive"))
      (node (ref "R42") (pin "2") (pinfunction "2_2") (pintype "passive"))
      (node (ref "R5") (pin "1") (pinfunction "1_1") (pintype "passive"))
    )
    (net (code "4") (name "BATLEVEL") (class "Default")
      (node (ref "C4") (pin "1") (pinfunction "1_1") (pintype "passive"))
      (node (ref "R15") (pin "1") (pinfunction "1_1") (pintype "passive"))
      (node (ref "R5") (pin "2") (pinfunction "2_2") (pintype "passive"))
      (node (ref "U1") (pin "4") (pinfunction "SENSOR_VP_4") (pintype "input"))
    )
    (net (code "5") (name "BUZ") (class "Default")
      (node (ref "R46") (pin "2") (pinfunction "2_2") (pintype "passive"))
      (node (ref "U1") (pin "37") (pinfunction "IO23_37") (pintype "bidirectional"))
    )
    (net (code "6") (name "CO") (class "Default")
      (node (ref "U1") (pin "6") (pinfunction "IO34_6") (pintype "input"))
      (node (ref "U5") (pin "H") (pinfunction "RS2_RED_H") (pintype "passive"))
    )
    (net (code "7") (name "CSN") (class "Default")
      (node (ref "RA-02_LORA") (pin "15") (pinfunction "NSS_15") (pintype "input"))
      (node (ref "U1") (pin "30") (pinfunction "IO18_30") (pintype "bidirectional"))
    )
    (net (code "8") (name "CSSD") (class "Default")
      (node (ref "R10") (pin "1") (pinfunction "1_1") (pintype "passive"))
      (node (ref "SD") (pin "2") (pinfunction "DAT3_2") (pintype "bidirectional"))
      (node (ref "U1") (pin "24") (pinfunction "IO2_24") (pintype "bidirectional"))
    )
    (net (code "9") (name "D+") (class "Default")
      (node (ref "CH340") (pin "5") (pinfunction "D+_5") (pintype "bidirectional"))
      (node (ref "MICRO-USB") (pin "3") (pinfunction "P3_3") (pintype "passive"))
    )
    (net (code "10") (name "D+T") (class "Default")
      (node (ref "CH1") (pin "5") (pinfunction "D+_5") (pintype "bidirectional"))
      (node (ref "MICRO-USB1") (pin "3") (pinfunction "P3_3") (pintype "passive"))
    )
    (net (code "11") (name "D-") (class "Default")
      (node (ref "CH340") (pin "6") (pinfunction "D-_6") (pintype "bidirectional"))
      (node (ref "MICRO-USB") (pin "2") (pinfunction "P2_2") (pintype "passive"))
    )
    (net (code "12") (name "D-T") (class "Default")
      (node (ref "CH1") (pin "6") (pinfunction "D-_6") (pintype "bidirectional"))
      (node (ref "MICRO-USB1") (pin "2") (pinfunction "P2_2") (pintype "passive"))
    )
    (net (code "13") (name "DIO0LORAT") (class "Default")
      (node (ref "RA-02_LORA1") (pin "5") (pinfunction "DI00_5") (pintype "bidirectional"))
      (node (ref "U2") (pin "24") (pinfunction "IO2_24") (pintype "bidirectional"))
    )
    (net (code "14") (name "DTR") (class "Default")
      (node (ref "CH340") (pin "13") (pinfunction "DTR_13") (pintype "bidirectional"))
      (node (ref "R6") (pin "1") (pinfunction "1_1") (pintype "passive"))
      (node (ref "T6") (pin "E") (pinfunction "E_E") (pintype "passive"))
    )
    (net (code "15") (name "DTRT") (class "Default")
      (node (ref "CH1") (pin "13") (pinfunction "DTR_13") (pintype "bidirectional"))
      (node (ref "R50") (pin "1") (pinfunction "1_1") (pintype "passive"))
      (node (ref "T2") (pin "E") (pinfunction "E_E") (pintype "passive"))
    )
    (net (code "16") (name "EN") (class "Default")
      (node (ref "C23") (pin "1") (pinfunction "1_1") (pintype "passive"))
      (node (ref "CPROGA") (pin "2") (pinfunction "5_2") (pintype "passive"))
      (node (ref "R1") (pin "1") (pinfunction "1_1") (pintype "passive"))
      (node (ref "U1") (pin "3") (pinfunction "EN_3") (pintype "input"))
    )
    (net (code "17") (name "ENE") (class "Default")
      (node (ref "CPROGE") (pin "2") (pinfunction "5_2") (pintype "passive"))
    )
    (net (code "18") (name "ENP") (class "Default")
      (node (ref "C16") (pin "1") (pinfunction "1_1") (pintype "passive"))
      (node (ref "CPROG") (pin "5") (pinfunction "2_5") (pintype "passive"))
      (node (ref "S4") (pin "2") (pinfunction "2_2") (pintype "passive"))
      (node (ref "T3") (pin "C") (pinfunction "C_C") (pintype "passive"))
    )
    (net (code "19") (name "ENT") (class "Default")
      (node (ref "C13") (pin "1") (pinfunction "1_1") (pintype "passive"))
      (node (ref "R37") (pin "1") (pinfunction "1_1") (pintype "passive"))
      (node (ref "T1") (pin "C") (pinfunction "C_C") (pintype "passive"))
      (node (ref "U2") (pin "3") (pinfunction "EN_3") (pintype "input"))
    )
    (net (code "20") (name "GND") (class "Default")
      (node (ref "BANDA") (pin "2") (pinfunction "5_2") (pintype "passive"))
      (node (ref "BMP180") (pin "7") (pinfunction "GND_7") (pintype "power_in"))
      (node (ref "C1") (pin "2") (pinfunction "2_2") (pintype "passive"))
      (node (ref "C10") (pin "2") (pinfunction "2_2") (pintype "passive"))
      (node (ref "C19") (pin "-") (pinfunction "-_-") (pintype "passive"))
      (node (ref "C2") (pin "2") (pinfunction "2_2") (pintype "passive"))
      (node (ref "C23") (pin "2") (pinfunction "2_2") (pintype "passive"))
      (node (ref "C24") (pin "2") (pinfunction "2_2") (pintype "passive"))
      (node (ref "C25") (pin "2") (pinfunction "2_2") (pintype "passive"))
      (node (ref "C26") (pin "2") (pinfunction "2_2") (pintype "passive"))
      (node (ref "C29") (pin "2") (pinfunction "2_2") (pintype "passive"))
      (node (ref "C3") (pin "2") (pinfunction "2_2") (pintype "passive"))
      (node (ref "C30") (pin "2") (pinfunction "2_2") (pintype "passive"))
      (node (ref "C31") (pin "2") (pinfunction "2_2") (pintype "passive"))
      (node (ref "C33") (pin "2") (pinfunction "2_2") (pintype "passive"))
      (node (ref "C34") (pin "2") (pinfunction "2_2") (pintype "passive"))
      (node (ref "C35") (pin "2") (pinfunction "2_2") (pintype "passive"))
      (node (ref "C4") (pin "2") (pinfunction "2_2") (pintype "passive"))
      (node (ref "C40") (pin "2") (pinfunction "2_2") (pintype "passive"))
      (node (ref "C43") (pin "2") (pinfunction "2_2") (pintype "passive"))
      (node (ref "C44") (pin "2") (pinfunction "2_2") (pintype "passive"))
      (node (ref "C45") (pin "2") (pinfunction "2_2") (pintype "passive"))
      (node (ref "C48") (pin "-") (pinfunction "-_-") (pintype "passive"))
      (node (ref "C49") (pin "2") (pinfunction "2_2") (pintype "passive"))
      (node (ref "C5") (pin "2") (pinfunction "2_2") (pintype "passive"))
      (node (ref "C56") (pin "2") (pinfunction "2_2") (pintype "passive"))
      (node (ref "C57") (pin "2") (pinfunction "2_2") (pintype "passive"))
      (node (ref "C58") (pin "2") (pinfunction "2_2") (pintype "passive"))
      (node (ref "CBAT") (pin "2") (pinfunction "2_2") (pintype "passive"))
      (node (ref "CCS811B") (pin "11") (pinfunction "EP_11") (pintype "power_in"))
      (node (ref "CPROGA") (pin "5") (pinfunction "2_5") (pintype "passive"))
      (node (ref "GPSBAT") (pin "2") (pinfunction "2_2") (pintype "passive"))
      (node (ref "HMC5983") (pin "11") (pinfunction "GND_11") (pintype "bidirectional"))
      (node (ref "HMC5983") (pin "9") (pinfunction "SOC_9") (pintype "bidirectional"))
      (node (ref "IC2") (pin "4") (pinfunction "GND_4") (pintype "bidirectional"))
      (node (ref "IC4") (pin "4") (pinfunction "GND_4") (pintype "bidirectional"))
      (node (ref "LED") (pin "C") (pinfunction "C_C") (pintype "passive"))
      (node (ref "LED1") (pin "C") (pinfunction "C_C") (pintype "passive"))
      (node (ref "LEDON") (pin "C") (pinfunction "C_C") (pintype "passive"))
      (node (ref "MPU6050") (pin "1") (pinfunction "CLKIN_1") (pintype "input"))
      (node (ref "MPU6050") (pin "11") (pinfunction "FSYNC_11") (pintype "input"))
      (node (ref "MPU6050") (pin "18") (pinfunction "GND_18") (pintype "power_in"))
      (node (ref "NEO-6M-GPS") (pin "10") (pinfunction "GND_10") (pintype "power_in"))
      (node (ref "NEO-6M-GPS") (pin "12") (pinfunction "GND_12") (pintype "power_in"))
      (node (ref "NEO-6M-GPS") (pin "13") (pinfunction "GND_13") (pintype "power_in"))
      (node (ref "NEO-6M-GPS") (pin "24") (pinfunction "GND_24") (pintype "power_in"))
      (node (ref "NEO-6M-GPS") (pin "7") (pinfunction "VDDUSB_7") (pintype "power_in"))
      (node (ref "Q1") (pin "2") (pinfunction "S_2") (pintype "passive"))
      (node (ref "Q2") (pin "2") (pinfunction "S_2") (pintype "passive"))
      (node (ref "Q4") (pin "2") (pinfunction "S_2") (pintype "passive"))
      (node (ref "R14") (pin "1") (pinfunction "1_1") (pintype "passive"))
      (node (ref "R15") (pin "2") (pinfunction "2_2") (pintype "passive"))
      (node (ref "R16") (pin "1") (pinfunction "1_1") (pintype "passive"))
      (node (ref "R23") (pin "1") (pinfunction "1_1") (pintype "passive"))
      (node (ref "R27") (pin "2") (pinfunction "2_2") (pintype "passive"))
      (node (ref "R3") (pin "1") (pinfunction "1_1") (pintype "passive"))
      (node (ref "R30") (pin "2") (pinfunction "2_2") (pintype "passive"))
      (node (ref "R31") (pin "1") (pinfunction "1_1") (pintype "passive"))
      (node (ref "R38") (pin "1") (pinfunction "1_1") (pintype "passive"))
      (node (ref "R40") (pin "1") (pinfunction "1_1") (pintype "passive"))
      (node (ref "R41") (pin "1") (pinfunction "1_1") (pintype "passive"))
      (node (ref "R45") (pin "1") (pinfunction "1_1") (pintype "passive"))
      (node (ref "RA-02_LORA") (pin "1") (pinfunction "GND_1") (pintype "power_in"))
      (node (ref "RA-02_LORA") (pin "16") (pinfunction "GND_16") (pintype "power_in"))
      (node (ref "RA-02_LORA") (pin "2") (pinfunction "GND_2") (pintype "power_in"))
      (node (ref "RA-02_LORA") (pin "9") (pinfunction "GND_9") (pintype "power_in"))
      (node (ref "S1") (pin "3") (pinfunction "3_3") (pintype "passive"))
      (node (ref "S2") (pin "3") (pinfunction "3_3") (pintype "passive"))
      (node (ref "S3") (pin "3") (pinfunction "3_3") (pintype "passive"))
      (node (ref "SD") (pin "6") (pinfunction "VSS_6") (pintype "passive"))
      (node (ref "SD") (pin "G1") (pinfunction "GND_G1") (pintype "passive"))
      (node (ref "SD") (pin "G2") (pinfunction "GND_G2") (pintype "passive"))
      (node (ref "SD") (pin "G3") (pinfunction "GND_G3") (pintype "passive"))
      (node (ref "SD") (pin "G4") (pinfunction "GND_G4") (pintype "passive"))
      (node (ref "SHT31") (pin "7") (pinfunction "R_7") (pintype "power_in"))
      (node (ref "SHT31") (pin "8") (pinfunction "VSS_8") (pintype "power_in"))
      (node (ref "SHT31") (pin "9") (pinfunction "EXP_9") (pintype "power_in"))
      (node (ref "T7") (pin "E") (pinfunction "E_E") (pintype "passive"))
      (node (ref "U1") (pin "1") (pinfunction "GND_1") (pintype "power_in"))
      (node (ref "U1") (pin "15") (pinfunction "GND_15") (pintype "power_in"))
      (node (ref "U1") (pin "38") (pinfunction "GND_38") (pintype "power_in"))
      (node (ref "U1") (pin "39_1") (pinfunction "GND_39_1") (pintype "power_in"))
      (node (ref "U1") (pin "39_10") (pinfunction "GND_39_10") (pintype "power_in"))
      (node (ref "U1") (pin "39_11") (pinfunction "GND_39_11") (pintype "power_in"))
      (node (ref "U1") (pin "39_12") (pinfunction "GND_39_12") (pintype "power_in"))
      (node (ref "U1") (pin "39_13") (pinfunction "GND_39_13") (pintype "power_in"))
      (node (ref "U1") (pin "39_14") (pinfunction "GND_39_14") (pintype "power_in"))
      (node (ref "U1") (pin "39_15") (pinfunction "GND_39_15") (pintype "power_in"))
      (node (ref "U1") (pin "39_16") (pinfunction "GND_39_16") (pintype "power_in"))
      (node (ref "U1") (pin "39_17") (pinfunction "GND_39_17") (pintype "power_in"))
      (node (ref "U1") (pin "39_18") (pinfunction "GND_39_18") (pintype "power_in"))
      (node (ref "U1") (pin "39_19") (pinfunction "GND_39_19") (pintype "power_in"))
      (node (ref "U1") (pin "39_2") (pinfunction "GND_39_2") (pintype "power_in"))
      (node (ref "U1") (pin "39_20") (pinfunction "GND_39_20") (pintype "power_in"))
      (node (ref "U1") (pin "39_21") (pinfunction "GND_39_21") (pintype "power_in"))
      (node (ref "U1") (pin "39_3") (pinfunction "GND_39_3") (pintype "power_in"))
      (node (ref "U1") (pin "39_4") (pinfunction "GND_39_4") (pintype "power_in"))
      (node (ref "U1") (pin "39_5") (pinfunction "GND_39_5") (pintype "power_in"))
      (node (ref "U1") (pin "39_6") (pinfunction "GND_39_6") (pintype "power_in"))
      (node (ref "U1") (pin "39_7") (pinfunction "GND_39_7") (pintype "power_in"))
      (node (ref "U1") (pin "39_8") (pinfunction "GND_39_8") (pintype "power_in"))
      (node (ref "U1") (pin "39_9") (pinfunction "GND_39_9") (pintype "power_in"))
      (node (ref "U5") (pin "B") (pinfunction "RH1/RS1_RED_B") (pintype "passive"))
      (node (ref "U5") (pin "F") (pinfunction "RS2_NH3_F") (pintype "passive"))
      (node (ref "U5") (pin "J") (pinfunction "RH1/RS1_OX_J") (pintype "passive"))
      (node (ref "U6") (pin "1") (pinfunction "A0_1") (pintype "bidirectional"))
      (node (ref "U6") (pin "2") (pinfunction "A1_2") (pintype "bidirectional"))
      (node (ref "U6") (pin "3") (pinfunction "A2_3") (pintype "bidirectional"))
      (node (ref "U6") (pin "4") (pinfunction "VSS_4") (pintype "power_in"))
      (node (ref "U6") (pin "7") (pinfunction "WP_7") (pintype "input"))
      (node (ref "X2") (pin "2@1") (pinfunction "GND_2@1") (pintype "passive"))
      (node (ref "X2") (pin "2@2") (pinfunction "GND_2@2") (pintype "passive"))
    )
    (net (code "21") (name "GNDE") (class "Default")
      (node (ref "BANDAE") (pin "5") (pinfunction "2_5") (pintype "passive"))
      (node (ref "C7") (pin "2") (pinfunction "2_2") (pintype "passive"))
      (node (ref "C8") (pin "2") (pinfunction "2_2") (pintype "passive"))
      (node (ref "C9") (pin "2") (pinfunction "2_2") (pintype "passive"))
      (node (ref "CPROGE") (pin "5") (pinfunction "2_5") (pintype "passive"))
      (node (ref "J1") (pin "S1") (pinfunction "2_S1") (pintype "passive"))
      (node (ref "J1") (pin "S2") (pinfunction "2_S2") (pintype "passive"))
      (node (ref "J1") (pin "S3") (pinfunction "2_S3") (pintype "passive"))
      (node (ref "J1") (pin "S4") (pinfunction "2_S4") (pintype "passive"))
      (node (ref "J2") (pin "S1") (pinfunction "2_S1") (pintype "passive"))
      (node (ref "J2") (pin "S2") (pinfunction "2_S2") (pintype "passive"))
      (node (ref "J2") (pin "S3") (pinfunction "2_S3") (pintype "passive"))
      (node (ref "J2") (pin "S4") (pinfunction "2_S4") (pintype "passive"))
      (node (ref "ONE") (pin "C") (pinfunction "C_C") (pintype "passive"))
      (node (ref "SBBRF") (pin "2") (pinfunction "C_2") (pintype "passive"))
      (node (ref "U$1") (pin "P$13") (pinfunction "GND._P$13") (pintype "bidirectional"))
      (node (ref "U$1") (pin "P$2") (pinfunction "GND_P$2") (pintype "bidirectional"))
      (node (ref "U$1") (pin "P$9") (pinfunction ".GND_P$9") (pintype "bidirectional"))
    )
    (net (code "22") (name "GNDP") (class "Default")
      (node (ref "C16") (pin "2") (pinfunction "2_2") (pintype "passive"))
      (node (ref "C17") (pin "2") (pinfunction "2_2") (pintype "passive"))
      (node (ref "C18") (pin "2") (pinfunction "2_2") (pintype "passive"))
      (node (ref "C22") (pin "2") (pinfunction "2_2") (pintype "passive"))
      (node (ref "C46") (pin "2") (pinfunction "2_2") (pintype "passive"))
      (node (ref "C47") (pin "2") (pinfunction "2_2") (pintype "passive"))
      (node (ref "C6") (pin "2") (pinfunction "2_2") (pintype "passive"))
      (node (ref "CH340") (pin "1") (pinfunction "GND_1") (pintype "bidirectional"))
      (node (ref "CPROG") (pin "2") (pinfunction "5_2") (pintype "passive"))
      (node (ref "MICRO-USB") (pin "5") (pinfunction "P5_5") (pintype "passive"))
      (node (ref "MICRO-USB") (pin "SH1") (pinfunction "SHIELD_SH1") (pintype "passive"))
      (node (ref "MICRO-USB") (pin "SH2") (pinfunction "SHIELD_SH2") (pintype "passive"))
      (node (ref "MICRO-USB") (pin "SH3") (pinfunction "SHIELD_SH3") (pintype "passive"))
      (node (ref "MICRO-USB") (pin "SH4") (pinfunction "SHIELD_SH4") (pintype "passive"))
      (node (ref "MICRO-USB") (pin "SH5") (pinfunction "SHIELD_SH5") (pintype "passive"))
      (node (ref "MICRO-USB") (pin "SH6") (pinfunction "SHIELD_SH6") (pintype "passive"))
      (node (ref "ONP") (pin "C") (pinfunction "C_C") (pintype "passive"))
      (node (ref "S4") (pin "1") (pinfunction "1_1") (pintype "passive"))
      (node (ref "S5") (pin "1") (pinfunction "1_1") (pintype "passive"))
      (node (ref "U4") (pin "2") (pinfunction "GND_2") (pintype "input"))
    )
    (net (code "23") (name "GNDT") (class "Default")
      (node (ref "C11") (pin "2") (pinfunction "2_2") (pintype "passive"))
      (node (ref "C13") (pin "2") (pinfunction "2_2") (pintype "passive"))
      (node (ref "C50") (pin "2") (pinfunction "2_2") (pintype "passive"))
      (node (ref "C51") (pin "2") (pinfunction "2_2") (pintype "passive"))
      (node (ref "C52") (pin "2") (pinfunction "2_2") (pintype "passive"))
      (node (ref "C53") (pin "2") (pinfunction "2_2") (pintype "passive"))
      (node (ref "C54") (pin "2") (pinfunction "2_2") (pintype "passive"))
      (node (ref "C55") (pin "2") (pinfunction "2_2") (pintype "passive"))
      (node (ref "CH1") (pin "1") (pinfunction "GND_1") (pintype "bidirectional"))
      (node (ref "LEDT") (pin "C") (pinfunction "C_C") (pintype "passive"))
      (node (ref "MICRO-USB1") (pin "5") (pinfunction "P5_5") (pintype "passive"))
      (node (ref "MICRO-USB1") (pin "SH1") (pinfunction "SHIELD_SH1") (pintype "passive"))
      (node (ref "MICRO-USB1") (pin "SH2") (pinfunction "SHIELD_SH2") (pintype "passive"))
      (node (ref "MICRO-USB1") (pin "SH3") (pinfunction "SHIELD_SH3") (pintype "passive"))
      (node (ref "MICRO-USB1") (pin "SH4") (pinfunction "SHIELD_SH4") (pintype "passive"))
      (node (ref "MICRO-USB1") (pin "SH5") (pinfunction "SHIELD_SH5") (pintype "passive"))
      (node (ref "MICRO-USB1") (pin "SH6") (pinfunction "SHIELD_SH6") (pintype "passive"))
      (node (ref "ONT") (pin "C") (pinfunction "C_C") (pintype "passive"))
      (node (ref "RA-02_LORA1") (pin "1") (pinfunction "GND_1") (pintype "power_in"))
      (node (ref "RA-02_LORA1") (pin "16") (pinfunction "GND_16") (pintype "power_in"))
      (node (ref "RA-02_LORA1") (pin "2") (pinfunction "GND_2") (pintype "power_in"))
      (node (ref "RA-02_LORA1") (pin "9") (pinfunction "GND_9") (pintype "power_in"))
      (node (ref "U2") (pin "1") (pinfunction "GND_1") (pintype "power_in"))
      (node (ref "U2") (pin "15") (pinfunction "GND_15") (pintype "power_in"))
      (node (ref "U2") (pin "38") (pinfunction "GND_38") (pintype "power_in"))
      (node (ref "U2") (pin "39_1") (pinfunction "GND_39_1") (pintype "power_in"))
      (node (ref "U2") (pin "39_10") (pinfunction "GND_39_10") (pintype "power_in"))
      (node (ref "U2") (pin "39_11") (pinfunction "GND_39_11") (pintype "power_in"))
      (node (ref "U2") (pin "39_12") (pinfunction "GND_39_12") (pintype "power_in"))
      (node (ref "U2") (pin "39_13") (pinfunction "GND_39_13") (pintype "power_in"))
      (node (ref "U2") (pin "39_14") (pinfunction "GND_39_14") (pintype "power_in"))
      (node (ref "U2") (pin "39_15") (pinfunction "GND_39_15") (pintype "power_in"))
      (node (ref "U2") (pin "39_16") (pinfunction "GND_39_16") (pintype "power_in"))
      (node (ref "U2") (pin "39_17") (pinfunction "GND_39_17") (pintype "power_in"))
      (node (ref "U2") (pin "39_18") (pinfunction "GND_39_18") (pintype "power_in"))
      (node (ref "U2") (pin "39_19") (pinfunction "GND_39_19") (pintype "power_in"))
      (node (ref "U2") (pin "39_2") (pinfunction "GND_39_2") (pintype "power_in"))
      (node (ref "U2") (pin "39_20") (pinfunction "GND_39_20") (pintype "power_in"))
      (node (ref "U2") (pin "39_21") (pinfunction "GND_39_21") (pintype "power_in"))
      (node (ref "U2") (pin "39_3") (pinfunction "GND_39_3") (pintype "power_in"))
      (node (ref "U2") (pin "39_4") (pinfunction "GND_39_4") (pintype "power_in"))
      (node (ref "U2") (pin "39_5") (pinfunction "GND_39_5") (pintype "power_in"))
      (node (ref "U2") (pin "39_6") (pinfunction "GND_39_6") (pintype "power_in"))
      (node (ref "U2") (pin "39_7") (pinfunction "GND_39_7") (pintype "power_in"))
      (node (ref "U2") (pin "39_8") (pinfunction "GND_39_8") (pintype "power_in"))
      (node (ref "U2") (pin "39_9") (pinfunction "GND_39_9") (pintype "power_in"))
      (node (ref "U3") (pin "2") (pinfunction "GND_2") (pintype "input"))
    )
    (net (code "24") (name "IO0") (class "Default")
      (node (ref "CPROGA") (pin "1") (pinfunction "6_1") (pintype "passive"))
      (node (ref "R2") (pin "1") (pinfunction "1_1") (pintype "passive"))
      (node (ref "U1") (pin "25") (pinfunction "IO0_25") (pintype "bidirectional"))
    )
    (net (code "25") (name "IO0E") (class "Default")
      (node (ref "CPROGE") (pin "1") (pinfunction "6_1") (pintype "passive"))
      (node (ref "U$1") (pin "P$14") (pinfunction "IO0_P$14") (pintype "bidirectional"))
    )
    (net (code "26") (name "IO0P") (class "Default")
      (node (ref "C17") (pin "1") (pinfunction "1_1") (pintype "passive"))
      (node (ref "CPROG") (pin "6") (pinfunction "1_6") (pintype "passive"))
      (node (ref "S5") (pin "2") (pinfunction "2_2") (pintype "passive"))
      (node (ref "T6") (pin "C") (pinfunction "C_C") (pintype "passive"))
    )
    (net (code "27") (name "IO0T") (class "Default")
      (node (ref "R43") (pin "1") (pinfunction "1_1") (pintype "passive"))
      (node (ref "T2") (pin "C") (pinfunction "C_C") (pintype "passive"))
      (node (ref "U2") (pin "25") (pinfunction "IO0_25") (pintype "bidirectional"))
    )
    (net (code "28") (name "IRQ") (class "Default")
      (node (ref "RA-02_LORA") (pin "5") (pinfunction "DI00_5") (pintype "bidirectional"))
      (node (ref "U1") (pin "11") (pinfunction "IO26_11") (pintype "bidirectional"))
    )
    (net (code "29") (name "LED") (class "Default")
      (node (ref "R4") (pin "1") (pinfunction "1_1") (pintype "passive"))
      (node (ref "U1") (pin "26") (pinfunction "IO4_26") (pintype "bidirectional"))
    )
    (net (code "30") (name "LEDT") (class "Default")
      (node (ref "R49") (pin "1") (pinfunction "1_1") (pintype "passive"))
      (node (ref "U2") (pin "14") (pinfunction "IO12_14") (pintype "bidirectional"))
    )
    (net (code "31") (name "LORARSTT") (class "Default")
      (node (ref "RA-02_LORA1") (pin "4") (pinfunction "RESET_4") (pintype "input"))
      (node (ref "U2") (pin "13") (pinfunction "IO14_13") (pintype "bidirectional"))
    )
    (net (code "32") (name "LRST") (class "Default")
      (node (ref "RA-02_LORA") (pin "4") (pinfunction "RESET_4") (pintype "input"))
      (node (ref "U1") (pin "14") (pinfunction "IO12_14") (pintype "bidirectional"))
    )
    (net (code "33") (name "M1") (class "Default")
      (node (ref "Q1") (pin "1") (pinfunction "G_1") (pintype "passive"))
      (node (ref "R45") (pin "2") (pinfunction "2_2") (pintype "passive"))
      (node (ref "U1") (pin "9") (pinfunction "IO33_9") (pintype "bidirectional"))
    )
    (net (code "34") (name "M2") (class "Default")
      (node (ref "Q4") (pin "1") (pinfunction "G_1") (pintype "passive"))
      (node (ref "R38") (pin "2") (pinfunction "2_2") (pintype "passive"))
      (node (ref "U1") (pin "8") (pinfunction "IO32_8") (pintype "bidirectional"))
    )
    (net (code "35") (name "M3") (class "Default")
      (node (ref "Q2") (pin "1") (pinfunction "G_1") (pintype "passive"))
      (node (ref "R23") (pin "2") (pinfunction "2_2") (pintype "passive"))
      (node (ref "U1") (pin "10") (pinfunction "IO25_10") (pintype "bidirectional"))
    )
    (net (code "36") (name "MISO") (class "Default")
      (node (ref "R22") (pin "1") (pinfunction "1_1") (pintype "passive"))
      (node (ref "RA-02_LORA") (pin "13") (pinfunction "MISO_13") (pintype "output"))
      (node (ref "SD") (pin "7") (pinfunction "DAT0_7") (pintype "bidirectional"))
      (node (ref "U1") (pin "31") (pinfunction "IO19_31") (pintype "bidirectional"))
    )
    (net (code "37") (name "MISOT") (class "Default")
      (node (ref "RA-02_LORA1") (pin "13") (pinfunction "MISO_13") (pintype "output"))
      (node (ref "U2") (pin "31") (pinfunction "IO19_31") (pintype "bidirectional"))
    )
    (net (code "38") (name "MOSI") (class "Default")
      (node (ref "R21") (pin "1") (pinfunction "1_1") (pintype "passive"))
      (node (ref "RA-02_LORA") (pin "14") (pinfunction "MOSI_14") (pintype "input"))
      (node (ref "SD") (pin "3") (pinfunction "CMD_3") (pintype "bidirectional"))
      (node (ref "U1") (pin "12") (pinfunction "IO27_12") (pintype "bidirectional"))
    )
    (net (code "39") (name "MOSIT") (class "Default")
      (node (ref "RA-02_LORA1") (pin "14") (pinfunction "MOSI_14") (pintype "input"))
      (node (ref "U2") (pin "37") (pinfunction "IO23_37") (pintype "bidirectional"))
    )
    (net (code "40") (name "NH3") (class "Default")
      (node (ref "U1") (pin "5") (pinfunction "SENSOR_VN_5") (pintype "input"))
      (node (ref "U5") (pin "D") (pinfunction "RS1_NH3_D") (pintype "passive"))
    )
    (net (code "41") (name "NO2") (class "Default")
      (node (ref "U1") (pin "7") (pinfunction "IO35_7") (pintype "input"))
      (node (ref "U5") (pin "A") (pinfunction "RS2_A") (pintype "passive"))
    )
    (net (code "42") (name "NSST") (class "Default")
      (node (ref "RA-02_LORA1") (pin "15") (pinfunction "NSS_15") (pintype "input"))
      (node (ref "U2") (pin "29") (pinfunction "IO5_29") (pintype "bidirectional"))
    )
    (net (code "43") (name "Net-(BUZ1-PadN)") (class "Default")
      (node (ref "BUZ1") (pin "N") (pinfunction "N_N") (pintype "passive"))
      (node (ref "T7") (pin "C") (pinfunction "C_C") (pintype "passive"))
    )
    (net (code "44") (name "Net-(C28-Pad2)") (class "Default")
      (node (ref "C28") (pin "2") (pinfunction "2_2") (pintype "passive"))
      (node (ref "R16") (pin "2") (pinfunction "2_2") (pintype "passive"))
    )
    (net (code "45") (name "Net-(C42-Pad2)") (class "Default")
      (node (ref "C42") (pin "2") (pinfunction "2_2") (pintype "passive"))
      (node (ref "R41") (pin "2") (pinfunction "2_2") (pintype "passive"))
    )
    (net (code "46") (name "Net-(CBAT-Pad1)") (class "Default")
      (node (ref "CBAT") (pin "1") (pinfunction "1_1") (pintype "passive"))
      (node (ref "ON-0FF") (pin "1") (pinfunction "1_1") (pintype "passive"))
    )
    (net (code "47") (name "Net-(CCS811B-ADDR)") (class "Default")
      (node (ref "CCS811B") (pin "1") (pinfunction "ADDR_1") (pintype "input"))
      (node (ref "JP2") (pin "2") (pinfunction "2_2") (pintype "passive"))
      (node (ref "R30") (pin "1") (pinfunction "1_1") (pintype "passive"))
    )
    (net (code "48") (name "Net-(CCS811B-PWM)") (class "Default")
      (node (ref "CCS811B") (pin "4") (pinfunction "PWM_4") (pintype "output"))
      (node (ref "CCS811B") (pin "5") (pinfunction "SENSE_5") (pintype "input"))
    )
    (net (code "49") (name "Net-(CCS811B-~{RESET})") (class "Default")
      (node (ref "CCS811B") (pin "2") (pinfunction "~{RESET}_2") (pintype "input"))
      (node (ref "R28") (pin "1") (pinfunction "1_1") (pintype "passive"))
    )
    (net (code "50") (name "Net-(CCS811B-~{WAKE})") (class "Default")
      (node (ref "CCS811B") (pin "7") (pinfunction "~{WAKE}_7") (pintype "input"))
      (node (ref "R31") (pin "2") (pinfunction "2_2") (pintype "passive"))
    )
    (net (code "51") (name "Net-(CH1-XI)") (class "Default")
      (node (ref "C52") (pin "1") (pinfunction "1_1") (pintype "passive"))
      (node (ref "CH1") (pin "7") (pinfunction "XI_7") (pintype "bidirectional"))
      (node (ref "Y3") (pin "3") (pinfunction "2_3") (pintype "passive"))
    )
    (net (code "52") (name "Net-(CH1-XO)") (class "Default")
      (node (ref "C53") (pin "1") (pinfunction "1_1") (pintype "passive"))
      (node (ref "CH1") (pin "8") (pinfunction "XO_8") (pintype "bidirectional"))
      (node (ref "Y3") (pin "1") (pinfunction "1_1") (pintype "passive"))
    )
    (net (code "53") (name "Net-(CH340-XI)") (class "Default")
      (node (ref "C47") (pin "1") (pinfunction "1_1") (pintype "passive"))
      (node (ref "CH340") (pin "7") (pinfunction "XI_7") (pintype "bidirectional"))
      (node (ref "Y2") (pin "3") (pinfunction "2_3") (pintype "passive"))
    )
    (net (code "54") (name "Net-(CH340-XO)") (class "Default")
      (node (ref "C46") (pin "1") (pinfunction "1_1") (pintype "passive"))
      (node (ref "CH340") (pin "8") (pinfunction "XO_8") (pintype "bidirectional"))
      (node (ref "Y2") (pin "1") (pinfunction "1_1") (pintype "passive"))
    )
    (net (code "55") (name "Net-(D7-I{slash}O)") (class "Default")
      (node (ref "D7") (pin "1") (pinfunction "I/O_1") (pintype "passive"))
      (node (ref "R33") (pin "2") (pinfunction "2_2") (pintype "passive"))
    )
    (net (code "56") (name "Net-(HMC5983-C1)") (class "Default")
      (node (ref "C33") (pin "1") (pinfunction "1_1") (pintype "passive"))
      (node (ref "HMC5983") (pin "10") (pinfunction "C1_10") (pintype "bidirectional"))
    )
    (net (code "57") (name "Net-(HMC5983-SETC)") (class "Default")
      (node (ref "C32") (pin "2") (pinfunction "2_2") (pintype "passive"))
      (node (ref "HMC5983") (pin "12") (pinfunction "SETC_12") (pintype "bidirectional"))
    )
    (net (code "58") (name "Net-(HMC5983-SETP)") (class "Default")
      (node (ref "C32") (pin "1") (pinfunction "1_1") (pintype "passive"))
      (node (ref "HMC5983") (pin "8") (pinfunction "SETP_8") (pintype "bidirectional"))
    )
    (net (code "59") (name "Net-(IC2-BS)") (class "Default")
      (node (ref "C27") (pin "2") (pinfunction "2_2") (pintype "passive"))
      (node (ref "IC2") (pin "1") (pinfunction "BS_1") (pintype "bidirectional"))
    )
    (net (code "60") (name "Net-(IC2-COMP)") (class "Default")
      (node (ref "C28") (pin "1") (pinfunction "1_1") (pintype "passive"))
      (node (ref "IC2") (pin "6") (pinfunction "COMP_6") (pintype "bidirectional"))
    )
    (net (code "61") (name "Net-(IC2-EN)") (class "Default")
      (node (ref "IC2") (pin "7") (pinfunction "EN_7") (pintype "bidirectional"))
      (node (ref "R19") (pin "1") (pinfunction "1_1") (pintype "passive"))
    )
    (net (code "62") (name "Net-(IC2-FB)") (class "Default")
      (node (ref "IC2") (pin "5") (pinfunction "FB_5") (pintype "bidirectional"))
      (node (ref "R13") (pin "1") (pinfunction "1_1") (pintype "passive"))
      (node (ref "R14") (pin "2") (pinfunction "2_2") (pintype "passive"))
    )
    (net (code "63") (name "Net-(IC2-SS)") (class "Default")
      (node (ref "C29") (pin "1") (pinfunction "1_1") (pintype "passive"))
      (node (ref "IC2") (pin "8") (pinfunction "SS_8") (pintype "bidirectional"))
    )
    (net (code "64") (name "Net-(IC2-SW)") (class "Default")
      (node (ref "C27") (pin "1") (pinfunction "1_1") (pintype "passive"))
      (node (ref "IC2") (pin "3") (pinfunction "SW_3") (pintype "bidirectional"))
      (node (ref "L1") (pin "1") (pinfunction "1_1") (pintype "passive"))
    )
    (net (code "65") (name "Net-(IC4-BS)") (class "Default")
      (node (ref "C41") (pin "2") (pinfunction "2_2") (pintype "passive"))
      (node (ref "IC4") (pin "1") (pinfunction "BS_1") (pintype "bidirectional"))
    )
    (net (code "66") (name "Net-(IC4-COMP)") (class "Default")
      (node (ref "C42") (pin "1") (pinfunction "1_1") (pintype "passive"))
      (node (ref "IC4") (pin "6") (pinfunction "COMP_6") (pintype "bidirectional"))
    )
    (net (code "67") (name "Net-(IC4-EN)") (class "Default")
      (node (ref "IC4") (pin "7") (pinfunction "EN_7") (pintype "bidirectional"))
      (node (ref "R42") (pin "1") (pinfunction "1_1") (pintype "passive"))
    )
    (net (code "68") (name "Net-(IC4-FB)") (class "Default")
      (node (ref "IC4") (pin "5") (pinfunction "FB_5") (pintype "bidirectional"))
      (node (ref "R39") (pin "1") (pinfunction "1_1") (pintype "passive"))
      (node (ref "R40") (pin "2") (pinfunction "2_2") (pintype "passive"))
    )
    (net (code "69") (name "Net-(IC4-SS)") (class "Default")
      (node (ref "C43") (pin "1") (pinfunction "1_1") (pintype "passive"))
      (node (ref "IC4") (pin "8") (pinfunction "SS_8") (pintype "bidirectional"))
    )
    (net (code "70") (name "Net-(IC4-SW)") (class "Default")
      (node (ref "C41") (pin "1") (pinfunction "1_1") (pintype "passive"))
      (node (ref "IC4") (pin "3") (pinfunction "SW_3") (pintype "bidirectional"))
      (node (ref "L3") (pin "1") (pinfunction "1_1") (pintype "passive"))
    )
    (net (code "71") (name "Net-(J1-Pad1)") (class "Default")
      (node (ref "J1") (pin "1") (pinfunction "1_1") (pintype "passive"))
      (node (ref "L5") (pin "2") (pinfunction "2_2") (pintype "passive"))
    )
    (net (code "72") (name "Net-(J2-Pad1)") (class "Default")
      (node (ref "J2") (pin "1") (pinfunction "1_1") (pintype "passive"))
      (node (ref "L4") (pin "2") (pinfunction "2_2") (pintype "passive"))
    )
    (net (code "73") (name "Net-(L2-Pad1)") (class "Default")
      (node (ref "L2") (pin "1") (pinfunction "1_1") (pintype "passive"))
      (node (ref "R32") (pin "2") (pinfunction "2_2") (pintype "passive"))
    )
    (net (code "74") (name "Net-(LED-PadA)") (class "Default")
      (node (ref "LED") (pin "A") (pinfunction "A_A") (pintype "passive"))
      (node (ref "R4") (pin "2") (pinfunction "2_2") (pintype "passive"))
    )
    (net (code "75") (name "Net-(LED1-PadA)") (class "Default")
      (node (ref "LED1") (pin "A") (pinfunction "A_A") (pintype "passive"))
      (node (ref "R8") (pin "1") (pinfunction "1_1") (pintype "passive"))
    )
    (net (code "76") (name "Net-(LEDON-PadA)") (class "Default")
      (node (ref "LEDON") (pin "A") (pinfunction "A_A") (pintype "passive"))
      (node (ref "R18") (pin "2") (pinfunction "2_2") (pintype "passive"))
    )
    (net (code "77") (name "Net-(LEDT-PadA)") (class "Default")
      (node (ref "LEDT") (pin "A") (pinfunction "A_A") (pintype "passive"))
      (node (ref "R49") (pin "2") (pinfunction "2_2") (pintype "passive"))
    )
    (net (code "78") (name "Net-(MPU6050-AD0)") (class "Default")
      (node (ref "JP1") (pin "2") (pinfunction "2_2") (pintype "passive"))
      (node (ref "MPU6050") (pin "9") (pinfunction "AD0_9") (pintype "input"))
      (node (ref "R3") (pin "2") (pinfunction "2_2") (pintype "passive"))
    )
    (net (code "79") (name "Net-(MPU6050-CPOUT)") (class "Default")
      (node (ref "C5") (pin "1") (pinfunction "1_1") (pintype "passive"))
      (node (ref "MPU6050") (pin "20") (pinfunction "CPOUT_20") (pintype "passive"))
    )
    (net (code "80") (name "Net-(MPU6050-REGOUT)") (class "Default")
      (node (ref "C3") (pin "1") (pinfunction "1_1") (pintype "passive"))
      (node (ref "MPU6050") (pin "10") (pinfunction "REGOUT_10") (pintype "passive"))
    )
    (net (code "81") (name "Net-(NEO-6M-GPS-RF_IN)") (class "Default")
      (node (ref "L2") (pin "2") (pinfunction "2_2") (pintype "passive"))
      (node (ref "NEO-6M-GPS") (pin "11") (pinfunction "RF_IN_11") (pintype "input"))
      (node (ref "X2") (pin "1") (pinfunction "1_1") (pintype "passive"))
    )
    (net (code "82") (name "Net-(NEO-6M-GPS-RSVD_8)") (class "Default")
      (node (ref "NEO-6M-GPS") (pin "8") (pinfunction "RSVD_8_8") (pintype "passive"))
      (node (ref "NEO-6M-GPS") (pin "9") (pinfunction "VCC_RF_9") (pintype "output"))
      (node (ref "R32") (pin "1") (pinfunction "1_1") (pintype "passive"))
    )
    (net (code "83") (name "Net-(NEO-6M-GPS-SCL2)") (class "Default")
      (node (ref "NEO-6M-GPS") (pin "19") (pinfunction "SCL2_19") (pintype "bidirectional"))
      (node (ref "U6") (pin "6") (pinfunction "SCL_6") (pintype "input"))
    )
    (net (code "84") (name "Net-(NEO-6M-GPS-SDA2)") (class "Default")
      (node (ref "NEO-6M-GPS") (pin "18") (pinfunction "SDA2_18") (pintype "bidirectional"))
      (node (ref "U6") (pin "5") (pinfunction "SDA_5") (pintype "bidirectional"))
    )
    (net (code "85") (name "Net-(NEO-6M-GPS-TIMEPULSE)") (class "Default")
      (node (ref "NEO-6M-GPS") (pin "3") (pinfunction "TIMEPULSE_3") (pintype "output"))
      (node (ref "R8") (pin "2") (pinfunction "2_2") (pintype "passive"))
    )
    (net (code "86") (name "Net-(NEO-6M-GPS-V_BCKP)") (class "Default")
      (node (ref "GPSBAT") (pin "1") (pinfunction "1_1") (pintype "passive"))
      (node (ref "NEO-6M-GPS") (pin "22") (pinfunction "V_BCKP_22") (pintype "power_in"))
      (node (ref "R33") (pin "1") (pinfunction "1_1") (pintype "passive"))
    )
    (net (code "87") (name "Net-(ONE-PadA)") (class "Default")
      (node (ref "ONE") (pin "A") (pinfunction "A_A") (pintype "passive"))
      (node (ref "R35") (pin "2") (pinfunction "2_2") (pintype "passive"))
    )
    (net (code "88") (name "Net-(ONP-PadA)") (class "Default")
      (node (ref "ONP") (pin "A") (pinfunction "A_A") (pintype "passive"))
      (node (ref "R34") (pin "2") (pinfunction "2_2") (pintype "passive"))
    )
    (net (code "89") (name "Net-(ONT-PadA)") (class "Default")
      (node (ref "ONT") (pin "A") (pinfunction "A_A") (pintype "passive"))
      (node (ref "R44") (pin "2") (pinfunction "2_2") (pintype "passive"))
    )
    (net (code "90") (name "Net-(Q1-D)") (class "Default")
      (node (ref "CMOT1") (pin "2") (pinfunction "2_2") (pintype "passive"))
      (node (ref "Q1") (pin "3") (pinfunction "D_3") (pintype "passive"))
    )
    (net (code "91") (name "Net-(Q2-D)") (class "Default")
      (node (ref "CMOT2") (pin "2") (pinfunction "2_2") (pintype "passive"))
      (node (ref "Q2") (pin "3") (pinfunction "D_3") (pintype "passive"))
    )
    (net (code "92") (name "Net-(Q4-D)") (class "Default")
      (node (ref "CMOT") (pin "2") (pinfunction "2_2") (pintype "passive"))
      (node (ref "Q4") (pin "3") (pinfunction "D_3") (pintype "passive"))
    )
    (net (code "93") (name "Net-(R6-Pad2)") (class "Default")
      (node (ref "R6") (pin "2") (pinfunction "2_2") (pintype "passive"))
      (node (ref "T3") (pin "B") (pinfunction "B_B") (pintype "passive"))
    )
    (net (code "94") (name "Net-(R7-Pad2)") (class "Default")
      (node (ref "R7") (pin "2") (pinfunction "2_2") (pintype "passive"))
      (node (ref "T6") (pin "B") (pinfunction "B_B") (pintype "passive"))
    )
    (net (code "95") (name "Net-(R46-Pad1)") (class "Default")
      (node (ref "R46") (pin "1") (pinfunction "1_1") (pintype "passive"))
      (node (ref "T7") (pin "B") (pinfunction "B_B") (pintype "passive"))
    )
    (net (code "96") (name "Net-(R50-Pad2)") (class "Default")
      (node (ref "R50") (pin "2") (pinfunction "2_2") (pintype "passive"))
      (node (ref "T1") (pin "B") (pinfunction "B_B") (pintype "passive"))
    )
    (net (code "97") (name "Net-(R51-Pad2)") (class "Default")
      (node (ref "R51") (pin "2") (pinfunction "2_2") (pintype "passive"))
      (node (ref "T2") (pin "B") (pinfunction "B_B") (pintype "passive"))
    )
    (net (code "98") (name "Net-(SBBRF-B)") (class "Default")
      (node (ref "L4") (pin "1") (pinfunction "1_1") (pintype "passive"))
      (node (ref "SBBRF") (pin "1") (pinfunction "B_1") (pintype "passive"))
    )
    (net (code "99") (name "Net-(SBBRF-E)") (class "Default")
      (node (ref "L5") (pin "1") (pinfunction "1_1") (pintype "passive"))
      (node (ref "L6") (pin "2") (pinfunction "2_2") (pintype "passive"))
      (node (ref "SBBRF") (pin "3") (pinfunction "E_3") (pintype "passive"))
    )
    (net (code "100") (name "Net-(SHT31-ADDR)") (class "Default")
      (node (ref "JP3") (pin "2") (pinfunction "2_2") (pintype "passive"))
      (node (ref "R27") (pin "1") (pinfunction "1_1") (pintype "passive"))
      (node (ref "SHT31") (pin "2") (pinfunction "ADDR_2") (pintype "input"))
    )
    (net (code "101") (name "Net-(U3-EN)") (class "Default")
      (node (ref "C55") (pin "1") (pinfunction "1_1") (pintype "passive"))
      (node (ref "D2") (pin "C") (pinfunction "C_C") (pintype "passive"))
      (node (ref "U3") (pin "1") (pinfunction "IN_1") (pintype "input"))
      (node (ref "U3") (pin "3") (pinfunction "EN_3") (pintype "input"))
    )
    (net (code "102") (name "Net-(U4-EN)") (class "Default")
      (node (ref "C22") (pin "1") (pinfunction "1_1") (pintype "passive"))
      (node (ref "D1") (pin "C") (pinfunction "C_C") (pintype "passive"))
      (node (ref "U4") (pin "1") (pinfunction "IN_1") (pintype "input"))
      (node (ref "U4") (pin "3") (pinfunction "EN_3") (pintype "input"))
    )
    (net (code "103") (name "Net-(U5-RH1_NH3)") (class "Default")
      (node (ref "R47") (pin "1") (pinfunction "1_1") (pintype "passive"))
      (node (ref "U5") (pin "C") (pinfunction "RH1_NH3_C") (pintype "passive"))
    )
    (net (code "104") (name "Net-(U5-RH2_NH3)") (class "Default")
      (node (ref "R52") (pin "1") (pinfunction "1_1") (pintype "passive"))
      (node (ref "U5") (pin "E") (pinfunction "RH2_NH3_E") (pintype "passive"))
      (node (ref "U5") (pin "G") (pinfunction "RH2_RED_G") (pintype "passive"))
    )
    (net (code "105") (name "Net-(U5-RH2_OX)") (class "Default")
      (node (ref "R48") (pin "1") (pinfunction "1_1") (pintype "passive"))
      (node (ref "U5") (pin "K") (pinfunction "RH2_OX_K") (pintype "passive"))
    )
    (net (code "106") (name "RSTP") (class "Default")
      (node (ref "CH340") (pin "14") (pinfunction "RTS_14") (pintype "bidirectional"))
      (node (ref "R7") (pin "1") (pinfunction "1_1") (pintype "passive"))
      (node (ref "T3") (pin "E") (pinfunction "E_E") (pintype "passive"))
    )
    (net (code "107") (name "RSTT") (class "Default")
      (node (ref "CH1") (pin "14") (pinfunction "RTS_14") (pintype "bidirectional"))
      (node (ref "R51") (pin "1") (pinfunction "1_1") (pintype "passive"))
      (node (ref "T1") (pin "E") (pinfunction "E_E") (pintype "passive"))
    )
    (net (code "108") (name "RX") (class "Default")
      (node (ref "CPROGA") (pin "3") (pinfunction "4_3") (pintype "passive"))
      (node (ref "U1") (pin "34") (pinfunction "RXD0_34") (pintype "bidirectional"))
    )
    (net (code "109") (name "RXGPS") (class "Default")
      (node (ref "NEO-6M-GPS") (pin "20") (pinfunction "TXD1_20") (pintype "output"))
      (node (ref "U1") (pin "27") (pinfunction "IO16_27") (pintype "bidirectional"))
    )
    (net (code "110") (name "RXP") (class "Default")
      (node (ref "CH340") (pin "3") (pinfunction "RX_3") (pintype "bidirectional"))
      (node (ref "CPROG") (pin "3") (pinfunction "4_3") (pintype "passive"))
    )
    (net (code "111") (name "RXT") (class "Default")
      (node (ref "CH1") (pin "2") (pinfunction "TX_2") (pintype "bidirectional"))
      (node (ref "U2") (pin "34") (pinfunction "RXD0_34") (pintype "bidirectional"))
    )
    (net (code "112") (name "RX{slash}SCL") (class "Default")
      (node (ref "BANDAE") (pin "3") (pinfunction "4_3") (pintype "passive"))
      (node (ref "CPROGE") (pin "3") (pinfunction "4_3") (pintype "passive"))
      (node (ref "U$1") (pin "P$11") (pinfunction "IO3/U0R_P$11") (pintype "bidirectional"))
    )
    (net (code "113") (name "S1") (class "Default")
      (node (ref "S1") (pin "1") (pinfunction "1_1") (pintype "passive"))
      (node (ref "U1") (pin "13") (pinfunction "IO14_13") (pintype "bidirectional"))
    )
    (net (code "114") (name "S2") (class "Default")
      (node (ref "S2") (pin "1") (pinfunction "1_1") (pintype "passive"))
      (node (ref "U1") (pin "23") (pinfunction "IO15_23") (pintype "bidirectional"))
    )
    (net (code "115") (name "S3") (class "Default")
      (node (ref "S3") (pin "1") (pinfunction "1_1") (pintype "passive"))
      (node (ref "U1") (pin "16") (pinfunction "IO13_16") (pintype "bidirectional"))
    )
    (net (code "116") (name "SCK") (class "Default")
      (node (ref "RA-02_LORA") (pin "12") (pinfunction "SCK_12") (pintype "input"))
      (node (ref "SD") (pin "5") (pinfunction "CLK_5") (pintype "input"))
      (node (ref "U1") (pin "29") (pinfunction "IO5_29") (pintype "bidirectional"))
    )
    (net (code "117") (name "SCKT") (class "Default")
      (node (ref "RA-02_LORA1") (pin "12") (pinfunction "SCK_12") (pintype "input"))
      (node (ref "U2") (pin "30") (pinfunction "IO18_30") (pintype "bidirectional"))
    )
    (net (code "118") (name "SCL") (class "Default")
      (node (ref "BANDA") (pin "4") (pinfunction "3_4") (pintype "passive"))
      (node (ref "BMP180") (pin "5") (pinfunction "SCL_5") (pintype "input"))
      (node (ref "CCS811B") (pin "10") (pinfunction "SCL_10") (pintype "input"))
      (node (ref "HMC5983") (pin "1") (pinfunction "SCL/SCK_1") (pintype "bidirectional"))
      (node (ref "MPU6050") (pin "23") (pinfunction "SCL_23") (pintype "input"))
      (node (ref "R20") (pin "2") (pinfunction "2_2") (pintype "passive"))
      (node (ref "SHT31") (pin "4") (pinfunction "SCL_4") (pintype "bidirectional"))
      (node (ref "U1") (pin "36") (pinfunction "IO22_36") (pintype "bidirectional"))
    )
    (net (code "119") (name "SDA") (class "Default")
      (node (ref "BANDA") (pin "3") (pinfunction "4_3") (pintype "passive"))
      (node (ref "BMP180") (pin "6") (pinfunction "SDA_6") (pintype "bidirectional"))
      (node (ref "CCS811B") (pin "9") (pinfunction "SDA_9") (pintype "bidirectional"))
      (node (ref "HMC5983") (pin "16") (pinfunction "SDA/SPI_SDI_16") (pintype "bidirectional"))
      (node (ref "MPU6050") (pin "24") (pinfunction "SDA_24") (pintype "bidirectional"))
      (node (ref "R17") (pin "2") (pinfunction "2_2") (pintype "passive"))
      (node (ref "SHT31") (pin "1") (pinfunction "SDA_1") (pintype "bidirectional"))
      (node (ref "U1") (pin "33") (pinfunction "IO21_33") (pintype "bidirectional"))
    )
    (net (code "120") (name "TX") (class "Default")
      (node (ref "CPROGA") (pin "4") (pinfunction "3_4") (pintype "passive"))
      (node (ref "U1") (pin "35") (pinfunction "TXD0_35") (pintype "bidirectional"))
    )
    (net (code "121") (name "TXGPS") (class "Default")
      (node (ref "NEO-6M-GPS") (pin "21") (pinfunction "RXD1_21") (pintype "input"))
      (node (ref "U1") (pin "28") (pinfunction "IO17_28") (pintype "bidirectional"))
    )
    (net (code "122") (name "TXP") (class "Default")
      (node (ref "CH340") (pin "2") (pinfunction "TX_2") (pintype "bidirectional"))
      (node (ref "CPROG") (pin "4") (pinfunction "3_4") (pintype "passive"))
    )
    (net (code "123") (name "TXT") (class "Default")
      (node (ref "CH1") (pin "3") (pinfunction "RX_3") (pintype "bidirectional"))
      (node (ref "U2") (pin "35") (pinfunction "TXD0_35") (pintype "bidirectional"))
    )
    (net (code "124") (name "TX{slash}SDA") (class "Default")
      (node (ref "BANDAE") (pin "4") (pinfunction "3_4") (pintype "passive"))
      (node (ref "CPROGE") (pin "4") (pinfunction "3_4") (pintype "passive"))
      (node (ref "U$1") (pin "P$10") (pinfunction "IO1/U0T_P$10") (pintype "bidirectional"))
    )
    (net (code "125") (name "VCC") (class "Default")
      (node (ref "BANDA") (pin "1") (pinfunction "6_1") (pintype "passive"))
      (node (ref "BMP180") (pin "2") (pinfunction "VDD_2") (pintype "power_in"))
      (node (ref "BMP180") (pin "3") (pinfunction "VDDIO_3") (pintype "power_in"))
      (node (ref "BUZ1") (pin "P") (pinfunction "P_P") (pintype "passive"))
      (node (ref "C1") (pin "1") (pinfunction "1_1") (pintype "passive"))
      (node (ref "C10") (pin "1") (pinfunction "1_1") (pintype "passive"))
      (node (ref "C2") (pin "1") (pinfunction "1_1") (pintype "passive"))
      (node (ref "C24") (pin "1") (pinfunction "1_1") (pintype "passive"))
      (node (ref "C25") (pin "1") (pinfunction "1_1") (pintype "passive"))
      (node (ref "C30") (pin "1") (pinfunction "1_1") (pintype "passive"))
      (node (ref "C31") (pin "1") (pinfunction "1_1") (pintype "passive"))
      (node (ref "C34") (pin "1") (pinfunction "1_1") (pintype "passive"))
      (node (ref "C35") (pin "1") (pinfunction "1_1") (pintype "passive"))
      (node (ref "C45") (pin "1") (pinfunction "1_1") (pintype "passive"))
      (node (ref "C48") (pin "+") (pinfunction "+_+") (pintype "passive"))
      (node (ref "C49") (pin "1") (pinfunction "1_1") (pintype "passive"))
      (node (ref "C56") (pin "1") (pinfunction "1_1") (pintype "passive"))
      (node (ref "C58") (pin "1") (pinfunction "1_1") (pintype "passive"))
      (node (ref "CCS811B") (pin "6") (pinfunction "VDD_6") (pintype "power_in"))
      (node (ref "CPROGA") (pin "6") (pinfunction "1_6") (pintype "passive"))
      (node (ref "D7") (pin "2") (pinfunction "GND_2") (pintype "passive"))
      (node (ref "HMC5983") (pin "13") (pinfunction "VDDIO_13") (pintype "bidirectional"))
      (node (ref "HMC5983") (pin "2") (pinfunction "VDD_2") (pintype "bidirectional"))
      (node (ref "HMC5983") (pin "4") (pinfunction "~{SPI_CS(S1})_4") (pintype "bidirectional"))
      (node (ref "HMC5983") (pin "6") (pinfunction "I2C/~{SPI}_6") (pintype "bidirectional"))
      (node (ref "JP1") (pin "1") (pinfunction "1_1") (pintype "passive"))
      (node (ref "JP2") (pin "1") (pinfunction "1_1") (pintype "passive"))
      (node (ref "JP3") (pin "1") (pinfunction "1_1") (pintype "passive"))
      (node (ref "L1") (pin "2") (pinfunction "2_2") (pintype "passive"))
      (node (ref "MPU6050") (pin "13") (pinfunction "VDD_13") (pintype "power_in"))
      (node (ref "MPU6050") (pin "8") (pinfunction "VLOGIC_8") (pintype "power_in"))
      (node (ref "NEO-6M-GPS") (pin "23") (pinfunction "VCC_23") (pintype "power_in"))
      (node (ref "R1") (pin "2") (pinfunction "2_2") (pintype "passive"))
      (node (ref "R10") (pin "2") (pinfunction "2_2") (pintype "passive"))
      (node (ref "R13") (pin "2") (pinfunction "2_2") (pintype "passive"))
      (node (ref "R17") (pin "1") (pinfunction "1_1") (pintype "passive"))
      (node (ref "R18") (pin "1") (pinfunction "1_1") (pintype "passive"))
      (node (ref "R2") (pin "2") (pinfunction "2_2") (pintype "passive"))
      (node (ref "R20") (pin "1") (pinfunction "1_1") (pintype "passive"))
      (node (ref "R21") (pin "2") (pinfunction "2_2") (pintype "passive"))
      (node (ref "R22") (pin "2") (pinfunction "2_2") (pintype "passive"))
      (node (ref "R28") (pin "2") (pinfunction "2_2") (pintype "passive"))
      (node (ref "RA-02_LORA") (pin "3") (pinfunction "3.3V_3") (pintype "power_in"))
      (node (ref "SD") (pin "4") (pinfunction "VDD_4") (pintype "power_in"))
      (node (ref "SHT31") (pin "5") (pinfunction "VDD_5") (pintype "power_in"))
      (node (ref "SHT31") (pin "6") (pinfunction "~{RESET}_6") (pintype "input"))
      (node (ref "U1") (pin "2") (pinfunction "3V3_2") (pintype "power_in"))
      (node (ref "U6") (pin "8") (pinfunction "VCC_8") (pintype "power_in"))
    )
    (net (code "126") (name "VCCE") (class "Default")
      (node (ref "BANDAE") (pin "6") (pinfunction "1_6") (pintype "passive"))
      (node (ref "CPROGE") (pin "6") (pinfunction "1_6") (pintype "passive"))
      (node (ref "R35") (pin "1") (pinfunction "1_1") (pintype "passive"))
    )
    (net (code "127") (name "VCCP") (class "Default")
      (node (ref "C18") (pin "1") (pinfunction "1_1") (pintype "passive"))
      (node (ref "C6") (pin "1") (pinfunction "1_1") (pintype "passive"))
      (node (ref "CH340") (pin "16") (pinfunction "VCC_16") (pintype "bidirectional"))
      (node (ref "CH340") (pin "4") (pinfunction "V3_4") (pintype "bidirectional"))
      (node (ref "CPROG") (pin "1") (pinfunction "6_1") (pintype "passive"))
      (node (ref "R34") (pin "1") (pinfunction "1_1") (pintype "passive"))
      (node (ref "U4") (pin "5") (pinfunction "OUT_5") (pintype "passive"))
    )
    (net (code "128") (name "VCCT") (class "Default")
      (node (ref "C11") (pin "1") (pinfunction "1_1") (pintype "passive"))
      (node (ref "C50") (pin "1") (pinfunction "1_1") (pintype "passive"))
      (node (ref "C51") (pin "1") (pinfunction "1_1") (pintype "passive"))
      (node (ref "C54") (pin "1") (pinfunction "1_1") (pintype "passive"))
      (node (ref "CH1") (pin "16") (pinfunction "VCC_16") (pintype "bidirectional"))
      (node (ref "CH1") (pin "4") (pinfunction "V3_4") (pintype "bidirectional"))
      (node (ref "R37") (pin "2") (pinfunction "2_2") (pintype "passive"))
      (node (ref "R43") (pin "2") (pinfunction "2_2") (pintype "passive"))
      (node (ref "R44") (pin "1") (pinfunction "1_1") (pintype "passive"))
      (node (ref "RA-02_LORA1") (pin "3") (pinfunction "3.3V_3") (pintype "power_in"))
      (node (ref "U2") (pin "2") (pinfunction "3V3_2") (pintype "power_in"))
      (node (ref "U3") (pin "5") (pinfunction "OUT_5") (pintype "passive"))
    )
    (net (code "129") (name "VIN") (class "Default")
      (node (ref "D1") (pin "A") (pinfunction "A_A") (pintype "passive"))
      (node (ref "MICRO-USB") (pin "1") (pinfunction "P1_1") (pintype "passive"))
    )
    (net (code "130") (name "VIN5V") (class "Default")
      (node (ref "BANDAE") (pin "1") (pinfunction "6_1") (pintype "passive"))
      (node (ref "BANDAE") (pin "2") (pinfunction "5_2") (pintype "passive"))
      (node (ref "C7") (pin "1") (pinfunction "1_1") (pintype "passive"))
      (node (ref "C8") (pin "1") (pinfunction "1_1") (pintype "passive"))
      (node (ref "C9") (pin "1") (pinfunction "1_1") (pintype "passive"))
      (node (ref "L6") (pin "1") (pinfunction "1_1") (pintype "passive"))
      (node (ref "U$1") (pin "P$1") (pinfunction "5V_P$1") (pintype "bidirectional"))
    )
    (net (code "131") (name "VINT") (class "Default")
      (node (ref "D2") (pin "A") (pinfunction "A_A") (pintype "passive"))
      (node (ref "MICRO-USB1") (pin "1") (pinfunction "P1_1") (pintype "passive"))
    )
    (net (code "132") (name "unconnected-(CCS811B-~{INT}-Pad3)") (class "Default")
      (node (ref "CCS811B") (pin "3") (pinfunction "~{INT}_3") (pintype "output"))
    )
    (net (code "133") (name "unconnected-(CH1-CTS-Pad9)") (class "Default")
      (node (ref "CH1") (pin "9") (pinfunction "CTS_9") (pintype "bidirectional"))
    )
    (net (code "134") (name "unconnected-(CH1-DCD-Pad12)") (class "Default")
      (node (ref "CH1") (pin "12") (pinfunction "DCD_12") (pintype "bidirectional"))
    )
    (net (code "135") (name "unconnected-(CH1-DSR-Pad10)") (class "Default")
      (node (ref "CH1") (pin "10") (pinfunction "DSR_10") (pintype "bidirectional"))
    )
    (net (code "136") (name "unconnected-(CH1-RI-Pad11)") (class "Default")
      (node (ref "CH1") (pin "11") (pinfunction "RI_11") (pintype "bidirectional"))
    )
    (net (code "137") (name "unconnected-(CH1-RS232-Pad15)") (class "Default")
      (node (ref "CH1") (pin "15") (pinfunction "RS232_15") (pintype "bidirectional"))
    )
    (net (code "138") (name "unconnected-(CH340-CTS-Pad9)") (class "Default")
      (node (ref "CH340") (pin "9") (pinfunction "CTS_9") (pintype "bidirectional"))
    )
    (net (code "139") (name "unconnected-(CH340-DCD-Pad12)") (class "Default")
      (node (ref "CH340") (pin "12") (pinfunction "DCD_12") (pintype "bidirectional"))
    )
    (net (code "140") (name "unconnected-(CH340-DSR-Pad10)") (class "Default")
      (node (ref "CH340") (pin "10") (pinfunction "DSR_10") (pintype "bidirectional"))
    )
    (net (code "141") (name "unconnected-(CH340-RI-Pad11)") (class "Default")
      (node (ref "CH340") (pin "11") (pinfunction "RI_11") (pintype "bidirectional"))
    )
    (net (code "142") (name "unconnected-(CH340-RS232-Pad15)") (class "Default")
      (node (ref "CH340") (pin "15") (pinfunction "RS232_15") (pintype "bidirectional"))
    )
    (net (code "143") (name "unconnected-(HMC5983-DRDY-Pad15)") (class "Default")
      (node (ref "HMC5983") (pin "15") (pinfunction "DRDY_15") (pintype "bidirectional"))
    )
    (net (code "144") (name "unconnected-(HMC5983-SPI_SDO-Pad5)") (class "Default")
      (node (ref "HMC5983") (pin "5") (pinfunction "SPI_SDO_5") (pintype "bidirectional"))
    )
    (net (code "145") (name "unconnected-(MICRO-USB-P4-Pad4)") (class "Default")
      (node (ref "MICRO-USB") (pin "4") (pinfunction "P4_4") (pintype "passive"))
    )
    (net (code "146") (name "unconnected-(MICRO-USB1-P4-Pad4)") (class "Default")
      (node (ref "MICRO-USB1") (pin "4") (pinfunction "P4_4") (pintype "passive"))
    )
    (net (code "147") (name "unconnected-(MPU6050-AUX_CL-Pad7)") (class "Default")
      (node (ref "MPU6050") (pin "7") (pinfunction "AUX_CL_7") (pintype "input"))
    )
    (net (code "148") (name "unconnected-(MPU6050-AUX_DA-Pad6)") (class "Default")
      (node (ref "MPU6050") (pin "6") (pinfunction "AUX_DA_6") (pintype "bidirectional"))
    )
    (net (code "149") (name "unconnected-(MPU6050-INT-Pad12)") (class "Default")
      (node (ref "MPU6050") (pin "12") (pinfunction "INT_12") (pintype "output"))
    )
    (net (code "150") (name "unconnected-(MPU6050-RESV-Pad19)") (class "Default")
      (node (ref "MPU6050") (pin "19") (pinfunction "RESV_19") (pintype "passive"))
    )
    (net (code "151") (name "unconnected-(MPU6050-RESV-Pad21)") (class "Default")
      (node (ref "MPU6050") (pin "21") (pinfunction "RESV_21") (pintype "passive"))
    )
    (net (code "152") (name "unconnected-(MPU6050-RESV-Pad22)") (class "Default")
      (node (ref "MPU6050") (pin "22") (pinfunction "RESV_22") (pintype "passive"))
    )
    (net (code "153") (name "unconnected-(NEO-6M-GPS-CFG_GPS0{slash}SCK-Pad16)") (class "Default")
      (node (ref "NEO-6M-GPS") (pin "16") (pinfunction "CFG_GPS0/SCK_16") (pintype "input"))
    )
    (net (code "154") (name "unconnected-(NEO-6M-GPS-EXTINT0-Pad4)") (class "Default")
      (node (ref "NEO-6M-GPS") (pin "4") (pinfunction "EXTINT0_4") (pintype "input"))
    )
    (net (code "155") (name "unconnected-(NEO-6M-GPS-MISO{slash}CFG_COM1-Pad15)") (class "Default")
      (node (ref "NEO-6M-GPS") (pin "15") (pinfunction "MISO/CFG_COM1_15") (pintype "input"))
    )
    (net (code "156") (name "unconnected-(NEO-6M-GPS-MOSI{slash}CFG_COM0-Pad14)") (class "Default")
      (node (ref "NEO-6M-GPS") (pin "14") (pinfunction "MOSI/CFG_COM0_14") (pintype "bidirectional"))
    )
    (net (code "157") (name "unconnected-(NEO-6M-GPS-RSVD_17-Pad17)") (class "Default")
      (node (ref "NEO-6M-GPS") (pin "17") (pinfunction "RSVD_17_17") (pintype "passive"))
    )
    (net (code "158") (name "unconnected-(NEO-6M-GPS-SS_N-Pad2)") (class "Default")
      (node (ref "NEO-6M-GPS") (pin "2") (pinfunction "SS_N_2") (pintype "input"))
    )
    (net (code "159") (name "unconnected-(NEO-6M-GPS-USB_DM-Pad5)") (class "Default")
      (node (ref "NEO-6M-GPS") (pin "5") (pinfunction "USB_DM_5") (pintype "bidirectional"))
    )
    (net (code "160") (name "unconnected-(NEO-6M-GPS-USB_DP-Pad6)") (class "Default")
      (node (ref "NEO-6M-GPS") (pin "6") (pinfunction "USB_DP_6") (pintype "bidirectional"))
    )
    (net (code "161") (name "unconnected-(RA-02_LORA-DI01-Pad6)") (class "Default")
      (node (ref "RA-02_LORA") (pin "6") (pinfunction "DI01_6") (pintype "bidirectional"))
    )
    (net (code "162") (name "unconnected-(RA-02_LORA-DI02-Pad7)") (class "Default")
      (node (ref "RA-02_LORA") (pin "7") (pinfunction "DI02_7") (pintype "bidirectional"))
    )
    (net (code "163") (name "unconnected-(RA-02_LORA-DI03-Pad8)") (class "Default")
      (node (ref "RA-02_LORA") (pin "8") (pinfunction "DI03_8") (pintype "bidirectional"))
    )
    (net (code "164") (name "unconnected-(RA-02_LORA-DI04-Pad10)") (class "Default")
      (node (ref "RA-02_LORA") (pin "10") (pinfunction "DI04_10") (pintype "bidirectional"))
    )
    (net (code "165") (name "unconnected-(RA-02_LORA-DI05-Pad11)") (class "Default")
      (node (ref "RA-02_LORA") (pin "11") (pinfunction "DI05_11") (pintype "bidirectional"))
    )
    (net (code "166") (name "unconnected-(RA-02_LORA1-DI01-Pad6)") (class "Default")
      (node (ref "RA-02_LORA1") (pin "6") (pinfunction "DI01_6") (pintype "bidirectional"))
    )
    (net (code "167") (name "unconnected-(RA-02_LORA1-DI02-Pad7)") (class "Default")
      (node (ref "RA-02_LORA1") (pin "7") (pinfunction "DI02_7") (pintype "bidirectional"))
    )
    (net (code "168") (name "unconnected-(RA-02_LORA1-DI03-Pad8)") (class "Default")
      (node (ref "RA-02_LORA1") (pin "8") (pinfunction "DI03_8") (pintype "bidirectional"))
    )
    (net (code "169") (name "unconnected-(RA-02_LORA1-DI04-Pad10)") (class "Default")
      (node (ref "RA-02_LORA1") (pin "10") (pinfunction "DI04_10") (pintype "bidirectional"))
    )
    (net (code "170") (name "unconnected-(RA-02_LORA1-DI05-Pad11)") (class "Default")
      (node (ref "RA-02_LORA1") (pin "11") (pinfunction "DI05_11") (pintype "bidirectional"))
    )
    (net (code "171") (name "unconnected-(SBBRF-C{slash}-Pad2@1)") (class "Default")
      (node (ref "SBBRF") (pin "2@1") (pinfunction "C/_2@1") (pintype "passive"))
    )
    (net (code "172") (name "unconnected-(SD-CD-Pad9)") (class "Default")
      (node (ref "SD") (pin "9") (pinfunction "CD_9") (pintype "input"))
    )
    (net (code "173") (name "unconnected-(SD-DAT1-Pad8)") (class "Default")
      (node (ref "SD") (pin "8") (pinfunction "DAT1_8") (pintype "bidirectional"))
    )
    (net (code "174") (name "unconnected-(SD-DAT2-Pad1)") (class "Default")
      (node (ref "SD") (pin "1") (pinfunction "DAT2_1") (pintype "bidirectional"))
    )
    (net (code "175") (name "unconnected-(SHT31-ALERT-Pad3)") (class "Default")
      (node (ref "SHT31") (pin "3") (pinfunction "ALERT_3") (pintype "output"))
    )
    (net (code "176") (name "unconnected-(U$1-3V3-PadP$16)") (class "Default")
      (node (ref "U$1") (pin "P$16") (pinfunction "3V3_P$16") (pintype "bidirectional"))
    )
    (net (code "177") (name "unconnected-(U$1-3V3.-PadP$12)") (class "Default")
      (node (ref "U$1") (pin "P$12") (pinfunction "3V3._P$12") (pintype "bidirectional"))
    )
    (net (code "178") (name "unconnected-(U$1-IO2-PadP$7)") (class "Default")
      (node (ref "U$1") (pin "P$7") (pinfunction "IO2_P$7") (pintype "bidirectional"))
    )
    (net (code "179") (name "unconnected-(U$1-IO4-PadP$8)") (class "Default")
      (node (ref "U$1") (pin "P$8") (pinfunction "IO4_P$8") (pintype "bidirectional"))
    )
    (net (code "180") (name "unconnected-(U$1-IO12-PadP$3)") (class "Default")
      (node (ref "U$1") (pin "P$3") (pinfunction "IO12_P$3") (pintype "bidirectional"))
    )
    (net (code "181") (name "unconnected-(U$1-IO13-PadP$4)") (class "Default")
      (node (ref "U$1") (pin "P$4") (pinfunction "IO13_P$4") (pintype "bidirectional"))
    )
    (net (code "182") (name "unconnected-(U$1-IO14-PadP$6)") (class "Default")
      (node (ref "U$1") (pin "P$6") (pinfunction "IO14_P$6") (pintype "bidirectional"))
    )
    (net (code "183") (name "unconnected-(U$1-IO15-PadP$5)") (class "Default")
      (node (ref "U$1") (pin "P$5") (pinfunction "IO15_P$5") (pintype "bidirectional"))
    )
    (net (code "184") (name "unconnected-(U$1-IO16-PadP$15)") (class "Default")
      (node (ref "U$1") (pin "P$15") (pinfunction "IO16_P$15") (pintype "bidirectional"))
    )
    (net (code "185") (name "unconnected-(U1-SCK{slash}CLK-Pad20)") (class "Default")
      (node (ref "U1") (pin "20") (pinfunction "SCK/CLK_20") (pintype "bidirectional"))
    )
    (net (code "186") (name "unconnected-(U1-SCS{slash}CMD-Pad19)") (class "Default")
      (node (ref "U1") (pin "19") (pinfunction "SCS/CMD_19") (pintype "bidirectional"))
    )
    (net (code "187") (name "unconnected-(U1-SDI{slash}SD1-Pad22)") (class "Default")
      (node (ref "U1") (pin "22") (pinfunction "SDI/SD1_22") (pintype "bidirectional"))
    )
    (net (code "188") (name "unconnected-(U1-SDO{slash}SD0-Pad21)") (class "Default")
      (node (ref "U1") (pin "21") (pinfunction "SDO/SD0_21") (pintype "bidirectional"))
    )
    (net (code "189") (name "unconnected-(U1-SHD{slash}SD2-Pad17)") (class "Default")
      (node (ref "U1") (pin "17") (pinfunction "SHD/SD2_17") (pintype "bidirectional"))
    )
    (net (code "190") (name "unconnected-(U1-SWP{slash}SD3-Pad18)") (class "Default")
      (node (ref "U1") (pin "18") (pinfunction "SWP/SD3_18") (pintype "bidirectional"))
    )
    (net (code "191") (name "unconnected-(U2-IO4-Pad26)") (class "Default")
      (node (ref "U2") (pin "26") (pinfunction "IO4_26") (pintype "bidirectional"))
    )
    (net (code "192") (name "unconnected-(U2-IO13-Pad16)") (class "Default")
      (node (ref "U2") (pin "16") (pinfunction "IO13_16") (pintype "bidirectional"))
    )
    (net (code "193") (name "unconnected-(U2-IO15-Pad23)") (class "Default")
      (node (ref "U2") (pin "23") (pinfunction "IO15_23") (pintype "bidirectional"))
    )
    (net (code "194") (name "unconnected-(U2-IO16-Pad27)") (class "Default")
      (node (ref "U2") (pin "27") (pinfunction "IO16_27") (pintype "bidirectional"))
    )
    (net (code "195") (name "unconnected-(U2-IO17-Pad28)") (class "Default")
      (node (ref "U2") (pin "28") (pinfunction "IO17_28") (pintype "bidirectional"))
    )
    (net (code "196") (name "unconnected-(U2-IO21-Pad33)") (class "Default")
      (node (ref "U2") (pin "33") (pinfunction "IO21_33") (pintype "bidirectional"))
    )
    (net (code "197") (name "unconnected-(U2-IO22-Pad36)") (class "Default")
      (node (ref "U2") (pin "36") (pinfunction "IO22_36") (pintype "bidirectional"))
    )
    (net (code "198") (name "unconnected-(U2-IO25-Pad10)") (class "Default")
      (node (ref "U2") (pin "10") (pinfunction "IO25_10") (pintype "bidirectional"))
    )
    (net (code "199") (name "unconnected-(U2-IO26-Pad11)") (class "Default")
      (node (ref "U2") (pin "11") (pinfunction "IO26_11") (pintype "bidirectional"))
    )
    (net (code "200") (name "unconnected-(U2-IO27-Pad12)") (class "Default")
      (node (ref "U2") (pin "12") (pinfunction "IO27_12") (pintype "bidirectional"))
    )
    (net (code "201") (name "unconnected-(U2-IO32-Pad8)") (class "Default")
      (node (ref "U2") (pin "8") (pinfunction "IO32_8") (pintype "bidirectional"))
    )
    (net (code "202") (name "unconnected-(U2-IO33-Pad9)") (class "Default")
      (node (ref "U2") (pin "9") (pinfunction "IO33_9") (pintype "bidirectional"))
    )
    (net (code "203") (name "unconnected-(U2-IO34-Pad6)") (class "Default")
      (node (ref "U2") (pin "6") (pinfunction "IO34_6") (pintype "input"))
    )
    (net (code "204") (name "unconnected-(U2-IO35-Pad7)") (class "Default")
      (node (ref "U2") (pin "7") (pinfunction "IO35_7") (pintype "input"))
    )
    (net (code "205") (name "unconnected-(U2-SCK{slash}CLK-Pad20)") (class "Default")
      (node (ref "U2") (pin "20") (pinfunction "SCK/CLK_20") (pintype "bidirectional"))
    )
    (net (code "206") (name "unconnected-(U2-SCS{slash}CMD-Pad19)") (class "Default")
      (node (ref "U2") (pin "19") (pinfunction "SCS/CMD_19") (pintype "bidirectional"))
    )
    (net (code "207") (name "unconnected-(U2-SDI{slash}SD1-Pad22)") (class "Default")
      (node (ref "U2") (pin "22") (pinfunction "SDI/SD1_22") (pintype "bidirectional"))
    )
    (net (code "208") (name "unconnected-(U2-SDO{slash}SD0-Pad21)") (class "Default")
      (node (ref "U2") (pin "21") (pinfunction "SDO/SD0_21") (pintype "bidirectional"))
    )
    (net (code "209") (name "unconnected-(U2-SENSOR_VN-Pad5)") (class "Default")
      (node (ref "U2") (pin "5") (pinfunction "SENSOR_VN_5") (pintype "input"))
    )
    (net (code "210") (name "unconnected-(U2-SENSOR_VP-Pad4)") (class "Default")
      (node (ref "U2") (pin "4") (pinfunction "SENSOR_VP_4") (pintype "input"))
    )
    (net (code "211") (name "unconnected-(U2-SHD{slash}SD2-Pad17)") (class "Default")
      (node (ref "U2") (pin "17") (pinfunction "SHD/SD2_17") (pintype "bidirectional"))
    )
    (net (code "212") (name "unconnected-(U2-SWP{slash}SD3-Pad18)") (class "Default")
      (node (ref "U2") (pin "18") (pinfunction "SWP/SD3_18") (pintype "bidirectional"))
    )
    (net (code "213") (name "unconnected-(U3-NC-Pad4)") (class "Default")
      (node (ref "U3") (pin "4") (pinfunction "NC_4") (pintype "no_connect"))
    )
    (net (code "214") (name "unconnected-(U4-NC-Pad4)") (class "Default")
      (node (ref "U4") (pin "4") (pinfunction "NC_4") (pintype "no_connect"))
    )
  )
)
